# V72_CIS.net
KiCad netlist of a schematic drawn in Altium Designer
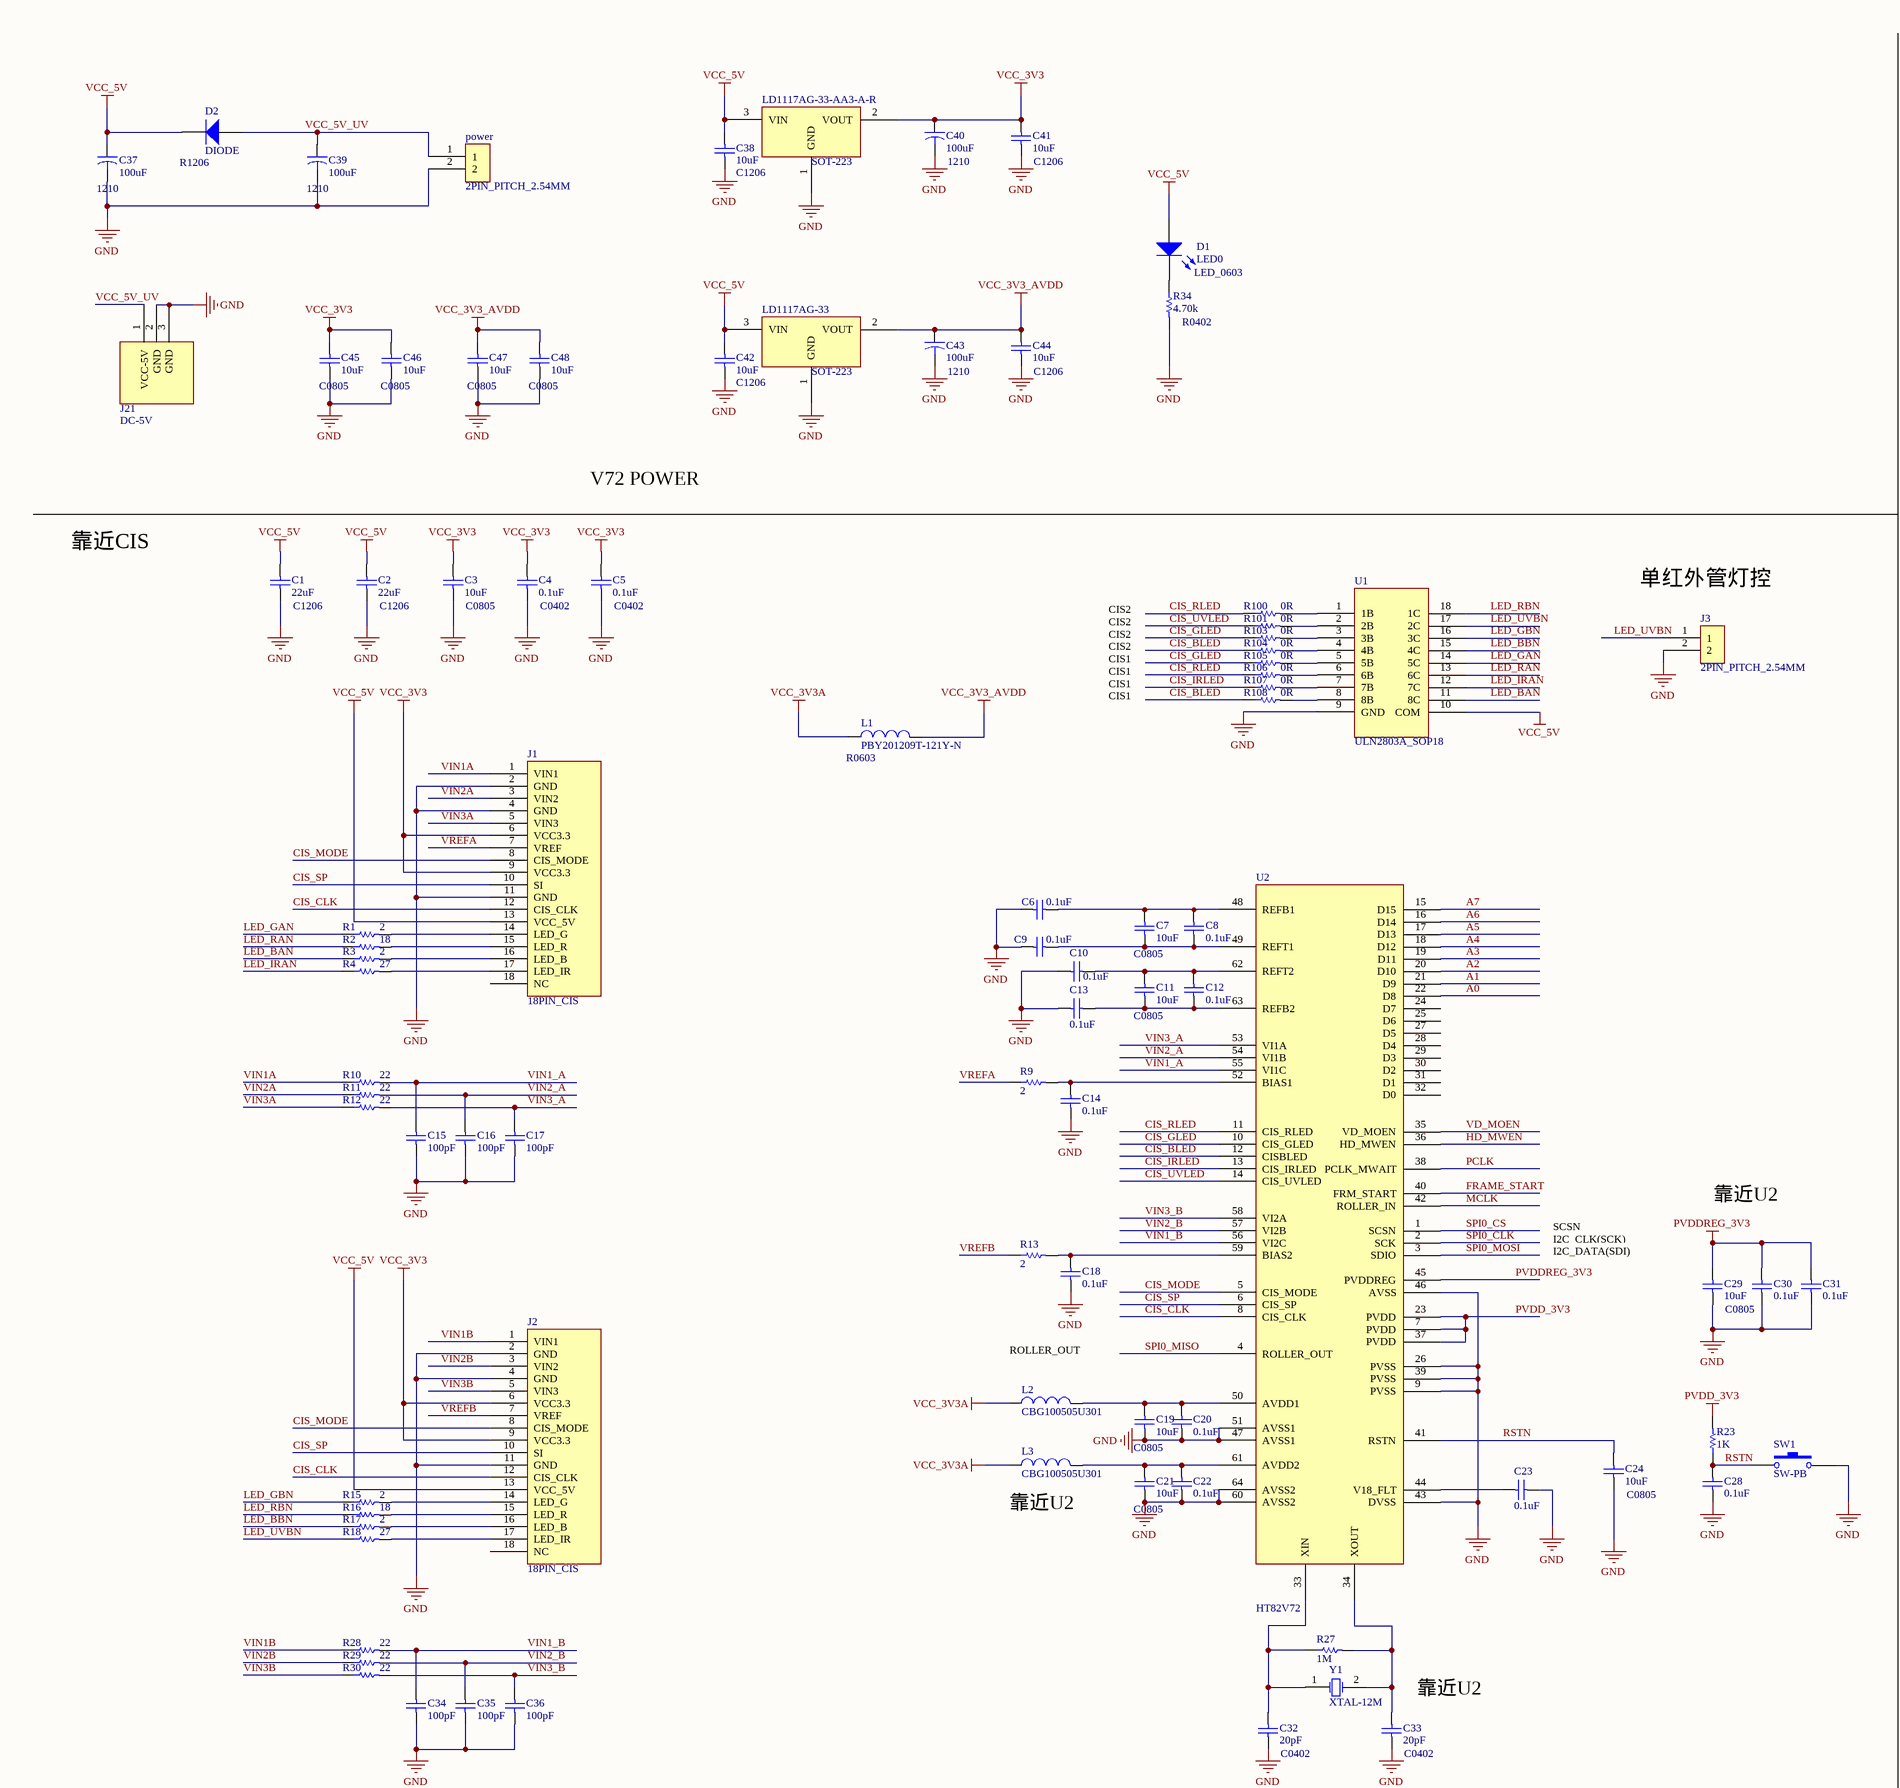
[diagram p0: V72单CIS.SchDoc, top left]
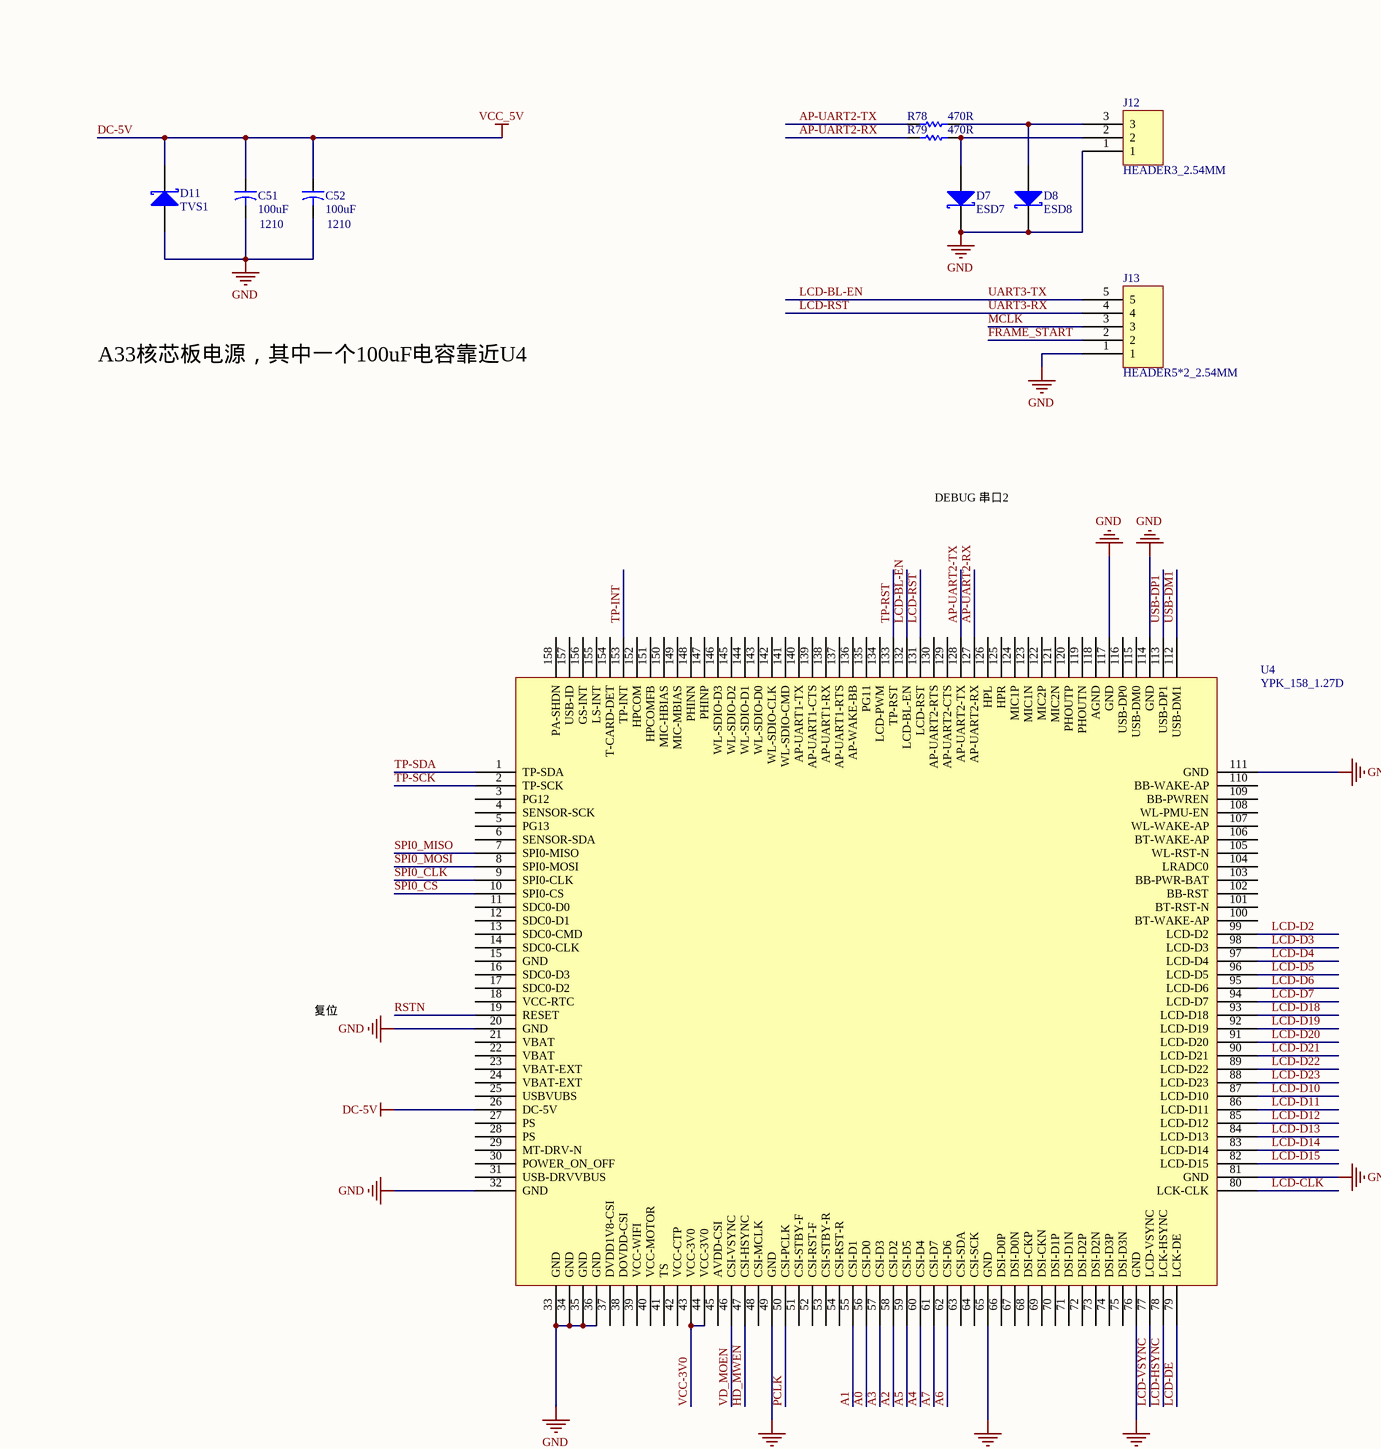
[diagram p1: V72单CIS.SchDoc, top middle]
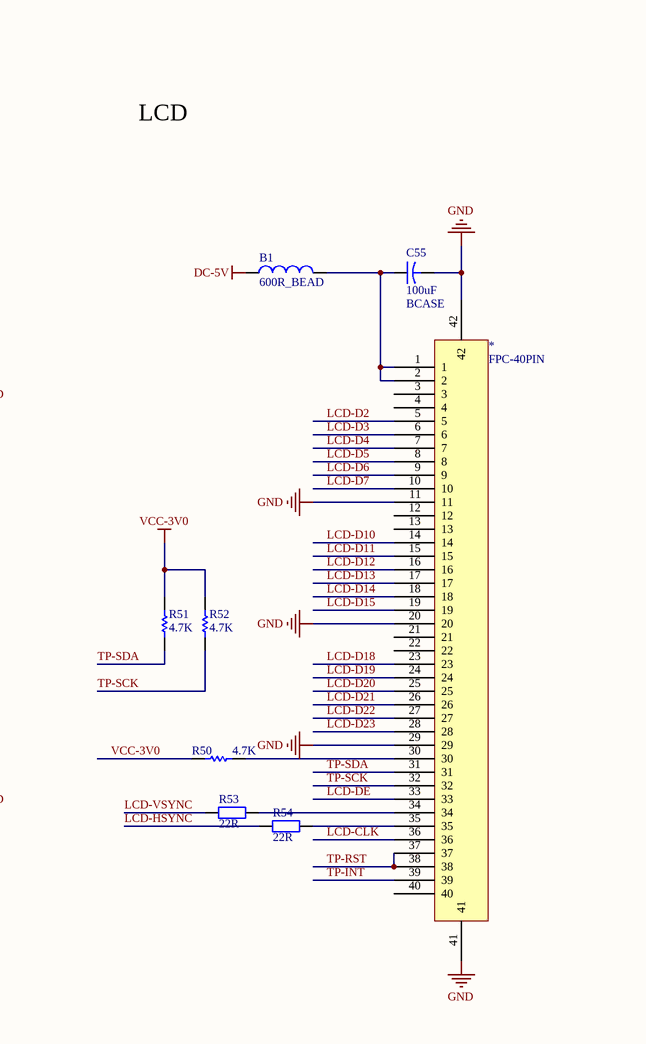
[diagram p2: V72单CIS.SchDoc, top right]
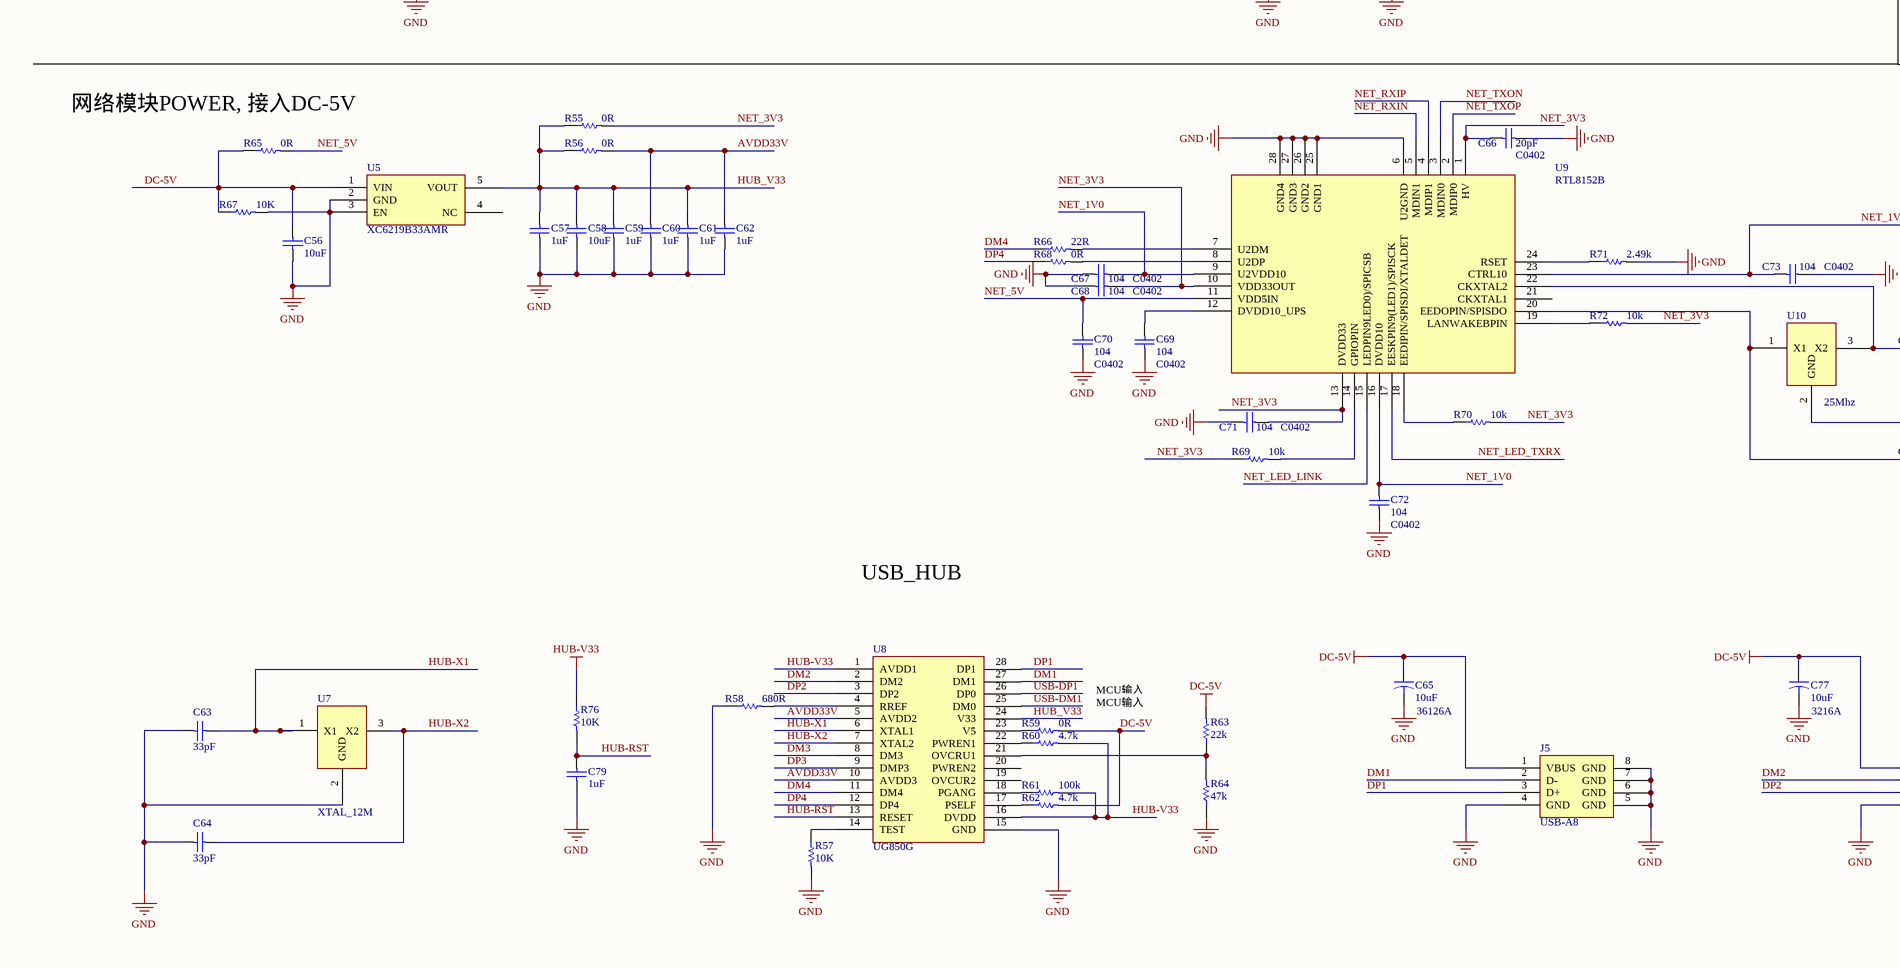
[diagram p3: V72单CIS.SchDoc, bottom left]
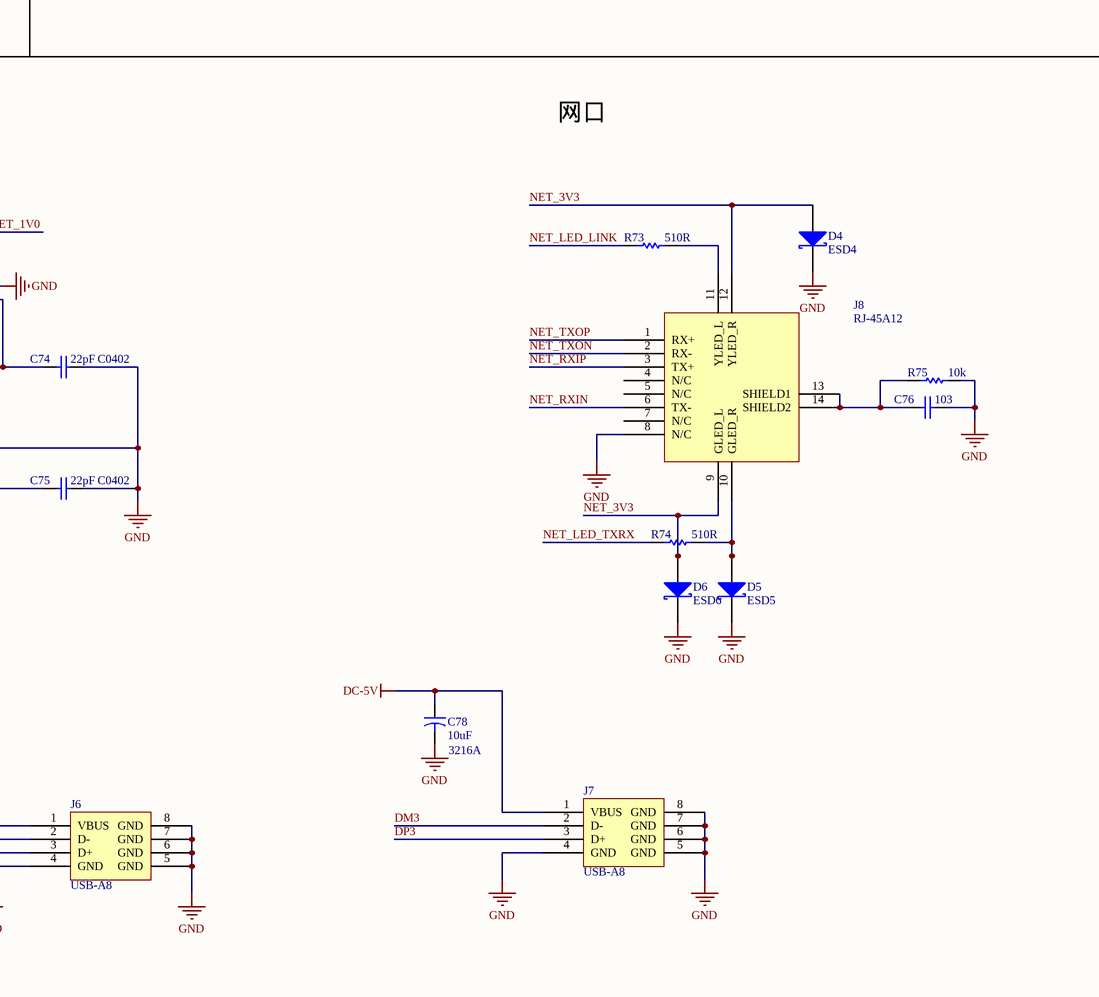
[diagram p4: V72单CIS.SchDoc, bottom middle]

(export (version "E")
  (design (tool "Eeschema 10.0.6"))
  (components
    (comp (ref "*")
      (value "FPC-40PIN")
      (footprint "FPC-40PIN")
      (libsource (lib "Integrated_Library") (part "FPC-40PIN"))
    )
    (comp (ref "B1")
      (value "600R_BEAD")
      (footprint "R0603")
      (description "Inductor")
      (fields (field (name "PUBLISHER") "Altium Limited"))
      (libsource (lib "Miscellaneous Devices") (part "Inductor"))
    )
    (comp (ref "C1")
      (value "22uF")
      (footprint "C1206")
      (description "Capacitor")
      (fields (field (name "PUBLISHER") "Altium Limited"))
      (libsource (lib "Miscellaneous Devices") (part "Cap"))
    )
    (comp (ref "C2")
      (value "22uF")
      (footprint "C1206")
      (description "Capacitor")
      (fields (field (name "PUBLISHER") "Altium Limited"))
      (libsource (lib "Miscellaneous Devices") (part "Cap"))
    )
    (comp (ref "C3")
      (value "10uF")
      (footprint "C0805")
      (description "Capacitor")
      (fields (field (name "PUBLISHER") "Altium Limited"))
      (libsource (lib "Miscellaneous Devices") (part "Cap"))
    )
    (comp (ref "C4")
      (value "0.1uF")
      (footprint "C0402")
      (description "Capacitor")
      (fields (field (name "PUBLISHER") "Altium Limited"))
      (libsource (lib "Miscellaneous Devices") (part "Cap"))
    )
    (comp (ref "C5")
      (value "0.1uF")
      (footprint "C0402")
      (description "Capacitor")
      (fields (field (name "PUBLISHER") "Altium Limited"))
      (libsource (lib "Miscellaneous Devices") (part "Cap"))
    )
    (comp (ref "C6")
      (value "0.1uF")
      (footprint "C0402")
      (description "Capacitor")
      (fields (field (name "PUBLISHER") "Altium Limited"))
      (libsource (lib "Miscellaneous Devices") (part "Cap"))
    )
    (comp (ref "C7")
      (value "10uF")
      (footprint "C0805")
      (description "Capacitor")
      (fields (field (name "PUBLISHER") "Altium Limited"))
      (libsource (lib "Miscellaneous Devices") (part "Cap"))
    )
    (comp (ref "C8")
      (value "0.1uF")
      (footprint "C0402")
      (description "Capacitor")
      (fields (field (name "PUBLISHER") "Altium Limited"))
      (libsource (lib "Miscellaneous Devices") (part "Cap"))
    )
    (comp (ref "C9")
      (value "0.1uF")
      (footprint "C0402")
      (description "Capacitor")
      (fields (field (name "PUBLISHER") "Altium Limited"))
      (libsource (lib "Miscellaneous Devices") (part "Cap"))
    )
    (comp (ref "C10")
      (value "0.1uF")
      (footprint "C0402")
      (description "Capacitor")
      (fields (field (name "PUBLISHER") "Altium Limited"))
      (libsource (lib "Miscellaneous Devices") (part "Cap"))
    )
    (comp (ref "C11")
      (value "10uF")
      (footprint "C0805")
      (description "Capacitor")
      (fields (field (name "PUBLISHER") "Altium Limited"))
      (libsource (lib "Miscellaneous Devices") (part "Cap"))
    )
    (comp (ref "C12")
      (value "0.1uF")
      (footprint "C0402")
      (description "Capacitor")
      (fields (field (name "PUBLISHER") "Altium Limited"))
      (libsource (lib "Miscellaneous Devices") (part "Cap"))
    )
    (comp (ref "C13")
      (value "0.1uF")
      (footprint "C0402")
      (description "Capacitor")
      (fields (field (name "PUBLISHER") "Altium Limited"))
      (libsource (lib "Miscellaneous Devices") (part "Cap"))
    )
    (comp (ref "C14")
      (value "0.1uF")
      (footprint "C0402")
      (description "Capacitor")
      (fields (field (name "PUBLISHER") "Altium Limited"))
      (libsource (lib "Miscellaneous Devices") (part "Cap"))
    )
    (comp (ref "C15")
      (value "100pF")
      (footprint "C0402")
      (description "Capacitor")
      (fields (field (name "PUBLISHER") "Altium Limited"))
      (libsource (lib "Miscellaneous Devices") (part "Cap"))
    )
    (comp (ref "C16")
      (value "100pF")
      (footprint "C0402")
      (description "Capacitor")
      (fields (field (name "PUBLISHER") "Altium Limited"))
      (libsource (lib "Miscellaneous Devices") (part "Cap"))
    )
    (comp (ref "C17")
      (value "100pF")
      (footprint "C0402")
      (description "Capacitor")
      (fields (field (name "PUBLISHER") "Altium Limited"))
      (libsource (lib "Miscellaneous Devices") (part "Cap"))
    )
    (comp (ref "C18")
      (value "0.1uF")
      (footprint "C0402")
      (description "Capacitor")
      (fields (field (name "PUBLISHER") "Altium Limited"))
      (libsource (lib "Miscellaneous Devices") (part "Cap"))
    )
    (comp (ref "C19")
      (value "10uF")
      (footprint "C0805")
      (description "Capacitor")
      (fields (field (name "PUBLISHER") "Altium Limited"))
      (libsource (lib "Miscellaneous Devices") (part "Cap"))
    )
    (comp (ref "C20")
      (value "0.1uF")
      (footprint "C0402")
      (description "Capacitor")
      (fields (field (name "PUBLISHER") "Altium Limited"))
      (libsource (lib "Miscellaneous Devices") (part "Cap"))
    )
    (comp (ref "C21")
      (value "10uF")
      (footprint "C0805")
      (description "Capacitor")
      (fields (field (name "PUBLISHER") "Altium Limited"))
      (libsource (lib "Miscellaneous Devices") (part "Cap"))
    )
    (comp (ref "C22")
      (value "0.1uF")
      (footprint "C0402")
      (description "Capacitor")
      (fields (field (name "PUBLISHER") "Altium Limited"))
      (libsource (lib "Miscellaneous Devices") (part "Cap"))
    )
    (comp (ref "C23")
      (value "0.1uF")
      (footprint "C0402")
      (description "Capacitor")
      (fields (field (name "PUBLISHER") "Altium Limited"))
      (libsource (lib "Miscellaneous Devices") (part "Cap"))
    )
    (comp (ref "C24")
      (value "10uF")
      (footprint "C0805")
      (description "Capacitor")
      (fields (field (name "PUBLISHER") "Altium Limited"))
      (libsource (lib "Miscellaneous Devices") (part "Cap"))
    )
    (comp (ref "C28")
      (value "0.1uF")
      (footprint "C0402")
      (description "Capacitor")
      (fields (field (name "PUBLISHER") "Altium Limited"))
      (libsource (lib "Miscellaneous Devices") (part "Cap"))
    )
    (comp (ref "C29")
      (value "10uF")
      (footprint "C0805")
      (description "Capacitor")
      (fields (field (name "PUBLISHER") "Altium Limited"))
      (libsource (lib "Miscellaneous Devices") (part "Cap"))
    )
    (comp (ref "C30")
      (value "0.1uF")
      (footprint "C0402")
      (description "Capacitor")
      (fields (field (name "PUBLISHER") "Altium Limited"))
      (libsource (lib "Miscellaneous Devices") (part "Cap"))
    )
    (comp (ref "C31")
      (value "0.1uF")
      (footprint "C0402")
      (description "Capacitor")
      (fields (field (name "PUBLISHER") "Altium Limited"))
      (libsource (lib "Miscellaneous Devices") (part "Cap"))
    )
    (comp (ref "C32")
      (value "20pF")
      (footprint "C0402")
      (description "Capacitor")
      (fields (field (name "PUBLISHER") "Altium Limited"))
      (libsource (lib "Miscellaneous Devices") (part "Cap"))
    )
    (comp (ref "C33")
      (value "20pF")
      (footprint "C0402")
      (description "Capacitor")
      (fields (field (name "PUBLISHER") "Altium Limited"))
      (libsource (lib "Miscellaneous Devices") (part "Cap"))
    )
    (comp (ref "C34")
      (value "100pF")
      (footprint "C0402")
      (description "Capacitor")
      (fields (field (name "PUBLISHER") "Altium Limited"))
      (libsource (lib "Miscellaneous Devices") (part "Cap"))
    )
    (comp (ref "C35")
      (value "100pF")
      (footprint "C0402")
      (description "Capacitor")
      (fields (field (name "PUBLISHER") "Altium Limited"))
      (libsource (lib "Miscellaneous Devices") (part "Cap"))
    )
    (comp (ref "C36")
      (value "100pF")
      (footprint "C0402")
      (description "Capacitor")
      (fields (field (name "PUBLISHER") "Altium Limited"))
      (libsource (lib "Miscellaneous Devices") (part "Cap"))
    )
    (comp (ref "C37")
      (value "100uF")
      (footprint "1210")
      (description "电容")
      (fields (field (name "PUBLISHER") "Altium Limited"))
      (libsource (lib "Miscellaneous Devices") (part "Cap2"))
    )
    (comp (ref "C38")
      (value "10uF")
      (footprint "C1206")
      (description "Capacitor")
      (fields (field (name "PUBLISHER") "Altium Limited"))
      (libsource (lib "Miscellaneous Devices") (part "Cap"))
    )
    (comp (ref "C39")
      (value "100uF")
      (footprint "1210")
      (description "Capacitor")
      (fields (field (name "PUBLISHER") "Altium Limited"))
      (libsource (lib "Miscellaneous Devices") (part "Cap2"))
    )
    (comp (ref "C40")
      (value "100uF")
      (footprint "1210")
      (description "Capacitor")
      (fields (field (name "PUBLISHER") "Altium Limited"))
      (libsource (lib "Miscellaneous Devices") (part "Cap2"))
    )
    (comp (ref "C41")
      (value "10uF")
      (footprint "C1206")
      (description "Capacitor")
      (fields (field (name "PUBLISHER") "Altium Limited"))
      (libsource (lib "Miscellaneous Devices") (part "Cap"))
    )
    (comp (ref "C42")
      (value "10uF")
      (footprint "C1206")
      (description "Capacitor")
      (fields (field (name "PUBLISHER") "Altium Limited"))
      (libsource (lib "Miscellaneous Devices") (part "Cap"))
    )
    (comp (ref "C43")
      (value "100uF")
      (footprint "1210")
      (description "Capacitor")
      (fields (field (name "PUBLISHER") "Altium Limited"))
      (libsource (lib "Miscellaneous Devices") (part "Cap2"))
    )
    (comp (ref "C44")
      (value "10uF")
      (footprint "C1206")
      (description "Capacitor")
      (fields (field (name "PUBLISHER") "Altium Limited"))
      (libsource (lib "Miscellaneous Devices") (part "Cap"))
    )
    (comp (ref "C45")
      (value "10uF")
      (footprint "C0805")
      (description "Capacitor")
      (fields (field (name "PUBLISHER") "Altium Limited"))
      (libsource (lib "Miscellaneous Devices") (part "Cap"))
    )
    (comp (ref "C46")
      (value "10uF")
      (footprint "C0805")
      (description "Capacitor")
      (fields (field (name "PUBLISHER") "Altium Limited"))
      (libsource (lib "Miscellaneous Devices") (part "Cap"))
    )
    (comp (ref "C47")
      (value "10uF")
      (footprint "C0805")
      (description "Capacitor")
      (fields (field (name "PUBLISHER") "Altium Limited"))
      (libsource (lib "Miscellaneous Devices") (part "Cap"))
    )
    (comp (ref "C48")
      (value "10uF")
      (footprint "C0805")
      (description "Capacitor")
      (fields (field (name "PUBLISHER") "Altium Limited"))
      (libsource (lib "Miscellaneous Devices") (part "Cap"))
    )
    (comp (ref "C51")
      (value "100uF")
      (footprint "1210")
      (description "Capacitor")
      (fields (field (name "PUBLISHER") "Altium Limited"))
      (libsource (lib "Miscellaneous Devices") (part "Cap2"))
    )
    (comp (ref "C52")
      (value "100uF")
      (footprint "1210")
      (description "Capacitor")
      (fields (field (name "PUBLISHER") "Altium Limited"))
      (libsource (lib "Miscellaneous Devices") (part "Cap2"))
    )
    (comp (ref "C55")
      (value "100uF")
      (footprint "BCASE")
      (description "Capacitor")
      (fields (field (name "PUBLISHER") "Altium Limited"))
      (libsource (lib "Miscellaneous Devices") (part "Cap2"))
    )
    (comp (ref "C56")
      (value "10uF")
      (footprint "0603A")
      (description "Capacitor")
      (fields (field (name "PUBLISHER") "Altium Limited"))
      (libsource (lib "Miscellaneous Devices") (part "Cap"))
    )
    (comp (ref "C57")
      (value "1uF")
      (footprint "0603A")
      (description "Capacitor")
      (fields (field (name "PUBLISHER") "Altium Limited"))
      (libsource (lib "Miscellaneous Devices") (part "Cap"))
    )
    (comp (ref "C58")
      (value "10uF")
      (footprint "0603A")
      (description "Capacitor")
      (fields (field (name "PUBLISHER") "Altium Limited"))
      (libsource (lib "Miscellaneous Devices") (part "Cap"))
    )
    (comp (ref "C59")
      (value "1uF")
      (footprint "0603A")
      (description "Capacitor")
      (fields (field (name "PUBLISHER") "Altium Limited"))
      (libsource (lib "Miscellaneous Devices") (part "Cap"))
    )
    (comp (ref "C60")
      (value "1uF")
      (footprint "0603A")
      (description "Capacitor")
      (fields (field (name "PUBLISHER") "Altium Limited"))
      (libsource (lib "Miscellaneous Devices") (part "Cap"))
    )
    (comp (ref "C61")
      (value "1uF")
      (footprint "0603A")
      (description "Capacitor")
      (fields (field (name "PUBLISHER") "Altium Limited"))
      (libsource (lib "Miscellaneous Devices") (part "Cap"))
    )
    (comp (ref "C62")
      (value "1uF")
      (footprint "0603A")
      (description "Capacitor")
      (fields (field (name "PUBLISHER") "Altium Limited"))
      (libsource (lib "Miscellaneous Devices") (part "Cap"))
    )
    (comp (ref "C63")
      (value "33pF")
      (footprint "0603A")
      (description "Capacitor")
      (fields (field (name "PUBLISHER") "Altium Limited"))
      (libsource (lib "Miscellaneous Devices") (part "Cap"))
    )
    (comp (ref "C64")
      (value "33pF")
      (footprint "0603A")
      (description "Capacitor")
      (fields (field (name "PUBLISHER") "Altium Limited"))
      (libsource (lib "Miscellaneous Devices") (part "Cap"))
    )
    (comp (ref "C65")
      (value "10uF")
      (footprint "36126A")
      (description "Capacitor")
      (fields (field (name "PUBLISHER") "Altium Limited"))
      (libsource (lib "Miscellaneous Devices") (part "Cap2"))
    )
    (comp (ref "C66")
      (value "20pF")
      (footprint "C0402")
      (description "Capacitor")
      (fields (field (name "PUBLISHER") "Altium Limited"))
      (libsource (lib "Miscellaneous Devices") (part "Cap"))
    )
    (comp (ref "C67")
      (value "104")
      (footprint "C0402")
      (description "Capacitor")
      (fields (field (name "PUBLISHER") "Altium Limited"))
      (libsource (lib "Miscellaneous Devices") (part "Cap"))
    )
    (comp (ref "C68")
      (value "104")
      (footprint "C0402")
      (description "Capacitor")
      (fields (field (name "PUBLISHER") "Altium Limited"))
      (libsource (lib "Miscellaneous Devices") (part "Cap"))
    )
    (comp (ref "C69")
      (value "104")
      (footprint "C0402")
      (description "Capacitor")
      (fields (field (name "PUBLISHER") "Altium Limited"))
      (libsource (lib "Miscellaneous Devices") (part "Cap"))
    )
    (comp (ref "C70")
      (value "104")
      (footprint "C0402")
      (description "Capacitor")
      (fields (field (name "PUBLISHER") "Altium Limited"))
      (libsource (lib "Miscellaneous Devices") (part "Cap"))
    )
    (comp (ref "C71")
      (value "104")
      (footprint "C0402")
      (description "Capacitor")
      (fields (field (name "PUBLISHER") "Altium Limited"))
      (libsource (lib "Miscellaneous Devices") (part "Cap"))
    )
    (comp (ref "C72")
      (value "104")
      (footprint "C0402")
      (description "Capacitor")
      (fields (field (name "PUBLISHER") "Altium Limited"))
      (libsource (lib "Miscellaneous Devices") (part "Cap"))
    )
    (comp (ref "C73")
      (value "104")
      (footprint "C0402")
      (description "Capacitor")
      (fields (field (name "PUBLISHER") "Altium Limited"))
      (libsource (lib "Miscellaneous Devices") (part "Cap"))
    )
    (comp (ref "C74")
      (value "22pF")
      (footprint "C0402")
      (description "Capacitor")
      (fields (field (name "PUBLISHER") "Altium Limited"))
      (libsource (lib "Miscellaneous Devices") (part "Cap"))
    )
    (comp (ref "C75")
      (value "22pF")
      (footprint "C0402")
      (description "Capacitor")
      (fields (field (name "PUBLISHER") "Altium Limited"))
      (libsource (lib "Miscellaneous Devices") (part "Cap"))
    )
    (comp (ref "C76")
      (value "103")
      (footprint "C0402")
      (description "Capacitor")
      (fields (field (name "PUBLISHER") "Altium Limited"))
      (libsource (lib "Miscellaneous Devices") (part "Cap"))
    )
    (comp (ref "C77")
      (value "10uF")
      (footprint "3216A")
      (description "Capacitor")
      (fields (field (name "PUBLISHER") "Altium Limited"))
      (libsource (lib "Miscellaneous Devices") (part "Cap2"))
    )
    (comp (ref "C78")
      (value "10uF")
      (footprint "3216A")
      (description "Capacitor")
      (fields (field (name "PUBLISHER") "Altium Limited"))
      (libsource (lib "Miscellaneous Devices") (part "Cap2"))
    )
    (comp (ref "C79")
      (value "1uF")
      (footprint "0603A")
      (description "Capacitor")
      (fields (field (name "PUBLISHER") "Altium Limited"))
      (libsource (lib "Miscellaneous Devices") (part "Cap"))
    )
    (comp (ref "D1")
      (value "LED0")
      (footprint "LED_0603")
      (description "Typical INFRARED GaAs LED")
      (fields (field (name "FOOTPRIINT") "LED_0603") (field (name "PUBLISHER") "Altium Limited"))
      (libsource (lib "Miscellaneous Devices") (part "LED0"))
    )
    (comp (ref "D2")
      (value "DIODE")
      (footprint "R1206")
      (description "Computer Diode")
      (fields (field (name "PUBLISHER") "Altium Limited"))
      (libsource (lib "Miscellaneous Devices") (part "Diode 1N4149"))
    )
    (comp (ref "D4")
      (value "ESD4")
      (footprint "LED_0603")
      (description "Silicon AF Schottky Diode for High-Speed Switching")
      (fields (field (name "PUBLISHER") "Altium Limited"))
      (libsource (lib "Miscellaneous Devices") (part "Diode BAS70"))
    )
    (comp (ref "D5")
      (value "ESD5")
      (footprint "LED_0603")
      (description "Silicon AF Schottky Diode for High-Speed Switching")
      (fields (field (name "PUBLISHER") "Altium Limited"))
      (libsource (lib "Miscellaneous Devices") (part "Diode BAS70"))
    )
    (comp (ref "D6")
      (value "ESD6")
      (footprint "LED_0603")
      (description "Silicon AF Schottky Diode for High-Speed Switching")
      (fields (field (name "PUBLISHER") "Altium Limited"))
      (libsource (lib "Miscellaneous Devices") (part "Diode BAS70"))
    )
    (comp (ref "D7")
      (value "ESD7")
      (footprint "LED_0603")
      (description "Silicon AF Schottky Diode for High-Speed Switching")
      (fields (field (name "PUBLISHER") "Altium Limited"))
      (libsource (lib "Miscellaneous Devices") (part "Diode BAS70"))
    )
    (comp (ref "D8")
      (value "ESD8")
      (footprint "LED_0603")
      (description "Silicon AF Schottky Diode for High-Speed Switching")
      (fields (field (name "PUBLISHER") "Altium Limited"))
      (libsource (lib "Miscellaneous Devices") (part "Diode BAS70"))
    )
    (comp (ref "D11")
      (value "TVS1")
      (footprint "SMB")
      (description "TVS二极管5V")
      (fields (field (name "PUBLISHER") "Altium Limited"))
      (libsource (lib "Miscellaneous Devices") (part "D Schottky"))
    )
    (comp (ref "J1")
      (value "18PIN_CIS")
      (footprint "18PIN_FPC")
      (libsource (lib "Integrated_Library") (part "18PIN_CIS"))
    )
    (comp (ref "J2")
      (value "18PIN_CIS")
      (footprint "18PIN_FPC")
      (libsource (lib "Integrated_Library") (part "18PIN_CIS"))
    )
    (comp (ref "J3")
      (value "2PIN_PITCH_2.54MM")
      (footprint "2PIN_PITCH_2.54MM")
      (libsource (lib "Integrated_Library") (part "2PIN_PITCH_2.54MM"))
    )
    (comp (ref "J5")
      (value "USB-A8")
      (footprint "USB-A8")
      (libsource (lib "Integrated_Library") (part "USB-A8"))
    )
    (comp (ref "J6")
      (value "USB-A8")
      (footprint "USB-A8")
      (libsource (lib "Integrated_Library") (part "USB-A8"))
    )
    (comp (ref "J7")
      (value "USB-A8")
      (footprint "USB-A8")
      (libsource (lib "Integrated_Library") (part "USB-A8"))
    )
    (comp (ref "J8")
      (value "RJ-45A12")
      (footprint "RJ-45A12")
      (libsource (lib "Integrated_Library") (part "RJ-45A12"))
    )
    (comp (ref "J12")
      (value "HEADER3_2.54MM")
      (footprint "HEADER3_2.54MM")
      (libsource (lib "Integrated_Library") (part "HEADER3_2.54MM"))
    )
    (comp (ref "J13")
      (value "HEADER5*2_2.54MM")
      (footprint "HEADER5_2.54MM")
      (libsource (lib "Integrated_Library") (part "HEADER5*2_2.54MM"))
    )
    (comp (ref "J21")
      (value "DC-5V")
      (footprint "DC-5V")
      (libsource (lib "Integrated_Library") (part "DC-5V"))
    )
    (comp (ref "L1")
      (value "PBY201209T-121Y-N")
      (footprint "R0603")
      (description "电感")
      (fields (field (name "PUBLISHER") "Altium Limited"))
      (libsource (lib "Miscellaneous Devices") (part "Inductor"))
    )
    (comp (ref "L2")
      (value "CBG100505U301")
      (footprint "R0603")
      (description "Inductor")
      (fields (field (name "PUBLISHER") "Altium Limited"))
      (libsource (lib "Miscellaneous Devices") (part "Inductor"))
    )
    (comp (ref "L3")
      (value "CBG100505U301")
      (footprint "R0603")
      (description "Inductor")
      (fields (field (name "PUBLISHER") "Altium Limited"))
      (libsource (lib "Miscellaneous Devices") (part "Inductor"))
    )
    (comp (ref "LD1117AG-33")
      (value "SOT-223")
      (footprint "SOT-223")
      (libsource (lib "Integrated_Library") (part "LD1117S33TR"))
    )
    (comp (ref "LD1117AG-33-AA3-A-R")
      (value "SOT-223")
      (footprint "SOT-223")
      (libsource (lib "Integrated_Library") (part "LD1117S33TR"))
    )
    (comp (ref "power")
      (value "2PIN_PITCH_2.54MM")
      (footprint "2PIN_PITCH_2.54MM")
      (libsource (lib "Integrated_Library") (part "2PIN_PITCH_2.54MM"))
    )
    (comp (ref "R1")
      (value "2")
      (footprint "R0603")
      (description "Resistor")
      (fields (field (name "PUBLISHER") "Altium Limited"))
      (libsource (lib "Miscellaneous Devices") (part "Res1"))
    )
    (comp (ref "R2")
      (value "18")
      (footprint "R0603")
      (description "Resistor")
      (fields (field (name "PUBLISHER") "Altium Limited"))
      (libsource (lib "Miscellaneous Devices") (part "Res1"))
    )
    (comp (ref "R3")
      (value "2")
      (footprint "R0603")
      (description "Resistor")
      (fields (field (name "PUBLISHER") "Altium Limited"))
      (libsource (lib "Miscellaneous Devices") (part "Res1"))
    )
    (comp (ref "R4")
      (value "27")
      (footprint "R0603")
      (description "Resistor")
      (fields (field (name "PUBLISHER") "Altium Limited"))
      (libsource (lib "Miscellaneous Devices") (part "Res1"))
    )
    (comp (ref "R9")
      (value "2")
      (footprint "R0603")
      (description "Resistor")
      (fields (field (name "PUBLISHER") "Altium Limited"))
      (libsource (lib "Miscellaneous Devices") (part "Res1"))
    )
    (comp (ref "R10")
      (value "22")
      (footprint "R0603")
      (description "Resistor")
      (fields (field (name "PUBLISHER") "Altium Limited"))
      (libsource (lib "Miscellaneous Devices") (part "Res1"))
    )
    (comp (ref "R11")
      (value "22")
      (footprint "R0603")
      (description "Resistor")
      (fields (field (name "PUBLISHER") "Altium Limited"))
      (libsource (lib "Miscellaneous Devices") (part "Res1"))
    )
    (comp (ref "R12")
      (value "22")
      (footprint "R0603")
      (description "Resistor")
      (fields (field (name "PUBLISHER") "Altium Limited"))
      (libsource (lib "Miscellaneous Devices") (part "Res1"))
    )
    (comp (ref "R13")
      (value "2")
      (footprint "R0603")
      (description "Resistor")
      (fields (field (name "PUBLISHER") "Altium Limited"))
      (libsource (lib "Miscellaneous Devices") (part "Res1"))
    )
    (comp (ref "R15")
      (value "2")
      (footprint "R0603")
      (description "Resistor")
      (fields (field (name "PUBLISHER") "Altium Limited"))
      (libsource (lib "Miscellaneous Devices") (part "Res1"))
    )
    (comp (ref "R16")
      (value "18")
      (footprint "R0603")
      (description "Resistor")
      (fields (field (name "PUBLISHER") "Altium Limited"))
      (libsource (lib "Miscellaneous Devices") (part "Res1"))
    )
    (comp (ref "R17")
      (value "2")
      (footprint "R0603")
      (description "Resistor")
      (fields (field (name "PUBLISHER") "Altium Limited"))
      (libsource (lib "Miscellaneous Devices") (part "Res1"))
    )
    (comp (ref "R18")
      (value "27")
      (footprint "R0603")
      (description "Resistor")
      (fields (field (name "PUBLISHER") "Altium Limited"))
      (libsource (lib "Miscellaneous Devices") (part "Res1"))
    )
    (comp (ref "R23")
      (value "1K")
      (footprint "R0603")
      (description "Resistor")
      (fields (field (name "PUBLISHER") "Altium Limited"))
      (libsource (lib "Miscellaneous Devices") (part "Res1"))
    )
    (comp (ref "R27")
      (value "1M")
      (footprint "R0603")
      (description "Resistor")
      (fields (field (name "PUBLISHER") "Altium Limited"))
      (libsource (lib "Miscellaneous Devices") (part "Res1"))
    )
    (comp (ref "R28")
      (value "22")
      (footprint "R0603")
      (description "Resistor")
      (fields (field (name "PUBLISHER") "Altium Limited"))
      (libsource (lib "Miscellaneous Devices") (part "Res1"))
    )
    (comp (ref "R29")
      (value "22")
      (footprint "R0603")
      (description "Resistor")
      (fields (field (name "PUBLISHER") "Altium Limited"))
      (libsource (lib "Miscellaneous Devices") (part "Res1"))
    )
    (comp (ref "R30")
      (value "22")
      (footprint "R0603")
      (description "Resistor")
      (fields (field (name "PUBLISHER") "Altium Limited"))
      (libsource (lib "Miscellaneous Devices") (part "Res1"))
    )
    (comp (ref "R34")
      (value "4.70k")
      (footprint "R0402")
      (description "Resistor")
      (fields (field (name "PUBLISHER") "Altium Limited"))
      (libsource (lib "Miscellaneous Devices") (part "Res1"))
    )
    (comp (ref "R50")
      (value "4.7K")
      (footprint "R0603")
      (description "Resistor")
      (fields (field (name "PUBLISHER") "Altium Limited"))
      (libsource (lib "Miscellaneous Devices") (part "Res1"))
    )
    (comp (ref "R51")
      (value "4.7K")
      (footprint "R0603")
      (description "Resistor")
      (fields (field (name "PUBLISHER") "Altium Limited"))
      (libsource (lib "Miscellaneous Devices") (part "Res1"))
    )
    (comp (ref "R52")
      (value "4.7K")
      (footprint "R0603")
      (description "Resistor")
      (fields (field (name "PUBLISHER") "Altium Limited"))
      (libsource (lib "Miscellaneous Devices") (part "Res1"))
    )
    (comp (ref "R53")
      (value "22R")
      (footprint "R0603")
      (description "Resistor")
      (fields (field (name "PUBLISHER") "Altium Limited"))
      (libsource (lib "Miscellaneous Devices") (part "Res2"))
    )
    (comp (ref "R54")
      (value "22R")
      (footprint "R0603")
      (description "Resistor")
      (fields (field (name "PUBLISHER") "Altium Limited"))
      (libsource (lib "Miscellaneous Devices") (part "Res2"))
    )
    (comp (ref "R55")
      (value "0R")
      (footprint "R0603")
      (description "Resistor")
      (fields (field (name "PUBLISHER") "Altium Limited"))
      (libsource (lib "Miscellaneous Devices") (part "Res1"))
    )
    (comp (ref "R56")
      (value "0R")
      (footprint "R0603")
      (description "Resistor")
      (fields (field (name "PUBLISHER") "Altium Limited"))
      (libsource (lib "Miscellaneous Devices") (part "Res1"))
    )
    (comp (ref "R57")
      (value "10K")
      (footprint "R0603")
      (description "Resistor")
      (fields (field (name "PUBLISHER") "Altium Limited"))
      (libsource (lib "Miscellaneous Devices") (part "Res1"))
    )
    (comp (ref "R58")
      (value "680R")
      (footprint "R0603")
      (description "Resistor")
      (fields (field (name "PUBLISHER") "Altium Limited"))
      (libsource (lib "Miscellaneous Devices") (part "Res1"))
    )
    (comp (ref "R59")
      (value "0R")
      (footprint "R0603")
      (description "Resistor")
      (fields (field (name "PUBLISHER") "Altium Limited"))
      (libsource (lib "Miscellaneous Devices") (part "Res1"))
    )
    (comp (ref "R60")
      (value "4.7k")
      (footprint "R0603")
      (description "Resistor")
      (fields (field (name "PUBLISHER") "Altium Limited"))
      (libsource (lib "Miscellaneous Devices") (part "Res1"))
    )
    (comp (ref "R61")
      (value "100k")
      (footprint "R0603")
      (description "Resistor")
      (fields (field (name "PUBLISHER") "Altium Limited"))
      (libsource (lib "Miscellaneous Devices") (part "Res1"))
    )
    (comp (ref "R62")
      (value "4.7k")
      (footprint "R0603")
      (description "Resistor")
      (fields (field (name "PUBLISHER") "Altium Limited"))
      (libsource (lib "Miscellaneous Devices") (part "Res1"))
    )
    (comp (ref "R63")
      (value "22k")
      (footprint "0603A")
      (description "Resistor")
      (fields (field (name "PUBLISHER") "Altium Limited"))
      (libsource (lib "Miscellaneous Devices") (part "Res1"))
    )
    (comp (ref "R64")
      (value "47k")
      (footprint "0603A")
      (description "Resistor")
      (fields (field (name "PUBLISHER") "Altium Limited"))
      (libsource (lib "Miscellaneous Devices") (part "Res1"))
    )
    (comp (ref "R65")
      (value "0R")
      (footprint "R0603")
      (description "Resistor")
      (fields (field (name "PUBLISHER") "Altium Limited"))
      (libsource (lib "Miscellaneous Devices") (part "Res1"))
    )
    (comp (ref "R66")
      (value "22R")
      (footprint "AXIAL-0.3")
      (description "Resistor")
      (fields (field (name "PUBLISHER") "Altium Limited"))
      (libsource (lib "Miscellaneous Devices") (part "Res1"))
    )
    (comp (ref "R67")
      (value "10K")
      (footprint "R0603")
      (description "Resistor")
      (fields (field (name "PUBLISHER") "Altium Limited"))
      (libsource (lib "Miscellaneous Devices") (part "Res1"))
    )
    (comp (ref "R68")
      (value "0R")
      (footprint "AXIAL-0.3")
      (description "Resistor")
      (fields (field (name "PUBLISHER") "Altium Limited"))
      (libsource (lib "Miscellaneous Devices") (part "Res1"))
    )
    (comp (ref "R69")
      (value "10k")
      (footprint "AXIAL-0.3")
      (description "Resistor")
      (fields (field (name "PUBLISHER") "Altium Limited"))
      (libsource (lib "Miscellaneous Devices") (part "Res1"))
    )
    (comp (ref "R70")
      (value "10k")
      (footprint "AXIAL-0.3")
      (description "Resistor")
      (fields (field (name "PUBLISHER") "Altium Limited"))
      (libsource (lib "Miscellaneous Devices") (part "Res1"))
    )
    (comp (ref "R71")
      (value "2.49k")
      (footprint "AXIAL-0.3")
      (description "Resistor")
      (fields (field (name "PUBLISHER") "Altium Limited"))
      (libsource (lib "Miscellaneous Devices") (part "Res1"))
    )
    (comp (ref "R72")
      (value "10k")
      (footprint "AXIAL-0.3")
      (description "Resistor")
      (fields (field (name "PUBLISHER") "Altium Limited"))
      (libsource (lib "Miscellaneous Devices") (part "Res1"))
    )
    (comp (ref "R73")
      (value "510R")
      (footprint "AXIAL-0.3")
      (description "Resistor")
      (fields (field (name "PUBLISHER") "Altium Limited"))
      (libsource (lib "Miscellaneous Devices") (part "Res1"))
    )
    (comp (ref "R74")
      (value "510R")
      (footprint "AXIAL-0.3")
      (description "Resistor")
      (fields (field (name "PUBLISHER") "Altium Limited"))
      (libsource (lib "Miscellaneous Devices") (part "Res1"))
    )
    (comp (ref "R75")
      (value "10k")
      (footprint "AXIAL-0.3")
      (description "Resistor")
      (fields (field (name "PUBLISHER") "Altium Limited"))
      (libsource (lib "Miscellaneous Devices") (part "Res1"))
    )
    (comp (ref "R76")
      (value "10K")
      (footprint "0603A")
      (description "Resistor")
      (fields (field (name "PUBLISHER") "Altium Limited"))
      (libsource (lib "Miscellaneous Devices") (part "Res1"))
    )
    (comp (ref "R78")
      (value "470R")
      (footprint "R0603")
      (description "Resistor")
      (fields (field (name "PUBLISHER") "Altium Limited"))
      (libsource (lib "Miscellaneous Devices") (part "Res1"))
    )
    (comp (ref "R79")
      (value "470R")
      (footprint "R0603")
      (description "Resistor")
      (fields (field (name "PUBLISHER") "Altium Limited"))
      (libsource (lib "Miscellaneous Devices") (part "Res1"))
    )
    (comp (ref "R100")
      (value "0R")
      (footprint "R0603")
      (description "Resistor")
      (fields (field (name "PUBLISHER") "Altium Limited"))
      (libsource (lib "Miscellaneous Devices") (part "Res1"))
    )
    (comp (ref "R101")
      (value "0R")
      (footprint "R0603")
      (description "Resistor")
      (fields (field (name "PUBLISHER") "Altium Limited"))
      (libsource (lib "Miscellaneous Devices") (part "Res1"))
    )
    (comp (ref "R103")
      (value "0R")
      (footprint "R0603")
      (description "Resistor")
      (fields (field (name "PUBLISHER") "Altium Limited"))
      (libsource (lib "Miscellaneous Devices") (part "Res1"))
    )
    (comp (ref "R104")
      (value "0R")
      (footprint "R0603")
      (description "Resistor")
      (fields (field (name "PUBLISHER") "Altium Limited"))
      (libsource (lib "Miscellaneous Devices") (part "Res1"))
    )
    (comp (ref "R105")
      (value "0R")
      (footprint "R0603")
      (description "Resistor")
      (fields (field (name "PUBLISHER") "Altium Limited"))
      (libsource (lib "Miscellaneous Devices") (part "Res1"))
    )
    (comp (ref "R106")
      (value "0R")
      (footprint "R0603")
      (description "Resistor")
      (fields (field (name "PUBLISHER") "Altium Limited"))
      (libsource (lib "Miscellaneous Devices") (part "Res1"))
    )
    (comp (ref "R107")
      (value "0R")
      (footprint "R0603")
      (description "Resistor")
      (fields (field (name "PUBLISHER") "Altium Limited"))
      (libsource (lib "Miscellaneous Devices") (part "Res1"))
    )
    (comp (ref "R108")
      (value "0R")
      (footprint "R0603")
      (description "Resistor")
      (fields (field (name "PUBLISHER") "Altium Limited"))
      (libsource (lib "Miscellaneous Devices") (part "Res1"))
    )
    (comp (ref "SW1")
      (value "SW-PB")
      (footprint "SWSW-2P-6.5M")
      (description "Switch")
      (fields (field (name "PUBLISHER") "Altium Limited"))
      (libsource (lib "Miscellaneous Devices") (part "SW-PB"))
    )
    (comp (ref "U1")
      (value "ULN2803A_SOP18")
      (footprint "ULN2803A")
      (libsource (lib "Integrated_Library") (part "ULN2803A_SOP18"))
    )
    (comp (ref "U2")
      (value "HT82V72")
      (footprint "HT82V72")
      (libsource (lib "Integrated_Library") (part "HT82V72"))
    )
    (comp (ref "U4")
      (value "YPK_158_1.27D")
      (footprint "YPK_158_1.27D")
      (libsource (lib "Integrated_Library") (part "YPK_158_1.27D"))
    )
    (comp (ref "U5")
      (value "XC6219B33AMR")
      (footprint "XC6219B33AMR")
      (libsource (lib "Integrated_Library") (part "XC6219B33AMR"))
    )
    (comp (ref "U7")
      (value "XTAL_12M")
      (footprint "XTAL")
      (libsource (lib "Integrated_Library") (part "XTAL_12M"))
    )
    (comp (ref "U8")
      (value "UG850G")
      (footprint "GL850G")
      (libsource (lib "Integrated_Library") (part "UG850G"))
    )
    (comp (ref "U9")
      (value "RTL8152B")
      (footprint "RTL8723BS")
      (libsource (lib "Integrated_Library") (part "RTL8152B"))
    )
    (comp (ref "U10")
      (value "25Mhz")
      (footprint "XTAL")
      (libsource (lib "Integrated_Library") (part "XTAL_12M"))
    )
    (comp (ref "Y1")
      (value "XTAL-12M")
      (footprint "XTAL8M")
      (description "Crystal Oscillator")
      (fields (field (name "PUBLISHER") "Altium Limited"))
      (libsource (lib "Miscellaneous Devices") (part "XTAL"))
    )
  )
  (nets
    (net (code "1") (name "/A0") (class "Default")
      (node (ref "U2") (pin "22") (pinfunction "D8_22") (pintype "passive"))
      (node (ref "U4") (pin "56") (pinfunction "CSI-D0_56") (pintype "passive"))
    )
    (net (code "2") (name "/A1") (class "Default")
      (node (ref "U2") (pin "21") (pinfunction "D9_21") (pintype "passive"))
      (node (ref "U4") (pin "55") (pinfunction "CSI-D1_55") (pintype "passive"))
    )
    (net (code "3") (name "/A2") (class "Default")
      (node (ref "U2") (pin "20") (pinfunction "D10_20") (pintype "passive"))
      (node (ref "U4") (pin "58") (pinfunction "CSI-D2_58") (pintype "passive"))
    )
    (net (code "4") (name "/A3") (class "Default")
      (node (ref "U2") (pin "19") (pinfunction "D11_19") (pintype "passive"))
      (node (ref "U4") (pin "57") (pinfunction "CSI-D3_57") (pintype "passive"))
    )
    (net (code "5") (name "/A4") (class "Default")
      (node (ref "U2") (pin "18") (pinfunction "D12_18") (pintype "passive"))
      (node (ref "U4") (pin "60") (pinfunction "CSI-D4_60") (pintype "passive"))
    )
    (net (code "6") (name "/A5") (class "Default")
      (node (ref "U2") (pin "17") (pinfunction "D13_17") (pintype "passive"))
      (node (ref "U4") (pin "59") (pinfunction "CSI-D5_59") (pintype "passive"))
    )
    (net (code "7") (name "/A6") (class "Default")
      (node (ref "U2") (pin "16") (pinfunction "D14_16") (pintype "passive"))
      (node (ref "U4") (pin "62") (pinfunction "CSI-D6_62") (pintype "passive"))
    )
    (net (code "8") (name "/A7") (class "Default")
      (node (ref "U2") (pin "15") (pinfunction "D15_15") (pintype "passive"))
      (node (ref "U4") (pin "61") (pinfunction "CSI-D7_61") (pintype "passive"))
    )
    (net (code "9") (name "/AP-UART2-RX") (class "Default")
      (node (ref "R79") (pin "1") (pinfunction "1_1") (pintype "passive"))
      (node (ref "U4") (pin "127") (pinfunction "AP-UART2-RX_127") (pintype "passive"))
    )
    (net (code "10") (name "/AP-UART2-TX") (class "Default")
      (node (ref "R78") (pin "1") (pinfunction "1_1") (pintype "passive"))
      (node (ref "U4") (pin "128") (pinfunction "AP-UART2-TX_128") (pintype "passive"))
    )
    (net (code "11") (name "/AVDD33V") (class "Default")
      (node (ref "C60") (pin "2") (pinfunction "2_2") (pintype "passive"))
      (node (ref "C62") (pin "2") (pinfunction "2_2") (pintype "passive"))
      (node (ref "R56") (pin "2") (pinfunction "2_2") (pintype "passive"))
      (node (ref "U8") (pin "10") (pinfunction "AVDD3_10") (pintype "passive"))
      (node (ref "U8") (pin "5") (pinfunction "AVDD2_5") (pintype "passive"))
    )
    (net (code "12") (name "/CIS_BLED") (class "Default")
      (node (ref "R104") (pin "1") (pinfunction "1_1") (pintype "passive"))
      (node (ref "R108") (pin "1") (pinfunction "1_1") (pintype "passive"))
      (node (ref "U2") (pin "12") (pinfunction "CISBLED_12") (pintype "passive"))
    )
    (net (code "13") (name "/CIS_CLK") (class "Default")
      (node (ref "J1") (pin "12") (pinfunction "CIS_CLK_12") (pintype "passive"))
      (node (ref "J2") (pin "12") (pinfunction "CIS_CLK_12") (pintype "passive"))
      (node (ref "U2") (pin "8") (pinfunction "CIS_CLK_8") (pintype "passive"))
    )
    (net (code "14") (name "/CIS_GLED") (class "Default")
      (node (ref "R103") (pin "1") (pinfunction "1_1") (pintype "passive"))
      (node (ref "R105") (pin "1") (pinfunction "1_1") (pintype "passive"))
      (node (ref "U2") (pin "10") (pinfunction "CIS_GLED_10") (pintype "passive"))
    )
    (net (code "15") (name "/CIS_IRLED") (class "Default")
      (node (ref "R107") (pin "1") (pinfunction "1_1") (pintype "passive"))
      (node (ref "U2") (pin "13") (pinfunction "CIS_IRLED_13") (pintype "passive"))
    )
    (net (code "16") (name "/CIS_MODE") (class "Default")
      (node (ref "J1") (pin "8") (pinfunction "CIS_MODE_8") (pintype "passive"))
      (node (ref "J2") (pin "8") (pinfunction "CIS_MODE_8") (pintype "passive"))
      (node (ref "U2") (pin "5") (pinfunction "CIS_MODE_5") (pintype "passive"))
    )
    (net (code "17") (name "/CIS_RLED") (class "Default")
      (node (ref "R100") (pin "1") (pinfunction "1_1") (pintype "passive"))
      (node (ref "R106") (pin "1") (pinfunction "1_1") (pintype "passive"))
      (node (ref "U2") (pin "11") (pinfunction "CIS_RLED_11") (pintype "passive"))
    )
    (net (code "18") (name "/CIS_SP") (class "Default")
      (node (ref "J1") (pin "10") (pinfunction "SI_10") (pintype "passive"))
      (node (ref "J2") (pin "10") (pinfunction "SI_10") (pintype "passive"))
      (node (ref "U2") (pin "6") (pinfunction "CIS_SP_6") (pintype "passive"))
    )
    (net (code "19") (name "/CIS_UVLED") (class "Default")
      (node (ref "R101") (pin "1") (pinfunction "1_1") (pintype "passive"))
      (node (ref "U2") (pin "14") (pinfunction "CIS_UVLED_14") (pintype "passive"))
    )
    (net (code "20") (name "/DM1") (class "Default")
      (node (ref "J5") (pin "2") (pinfunction "D-_2") (pintype "passive"))
      (node (ref "U8") (pin "27") (pinfunction "DM1_27") (pintype "passive"))
    )
    (net (code "21") (name "/DM2") (class "Default")
      (node (ref "J6") (pin "2") (pinfunction "D-_2") (pintype "passive"))
      (node (ref "U8") (pin "2") (pinfunction "DM2_2") (pintype "passive"))
    )
    (net (code "22") (name "/DM3") (class "Default")
      (node (ref "J7") (pin "2") (pinfunction "D-_2") (pintype "passive"))
      (node (ref "U8") (pin "8") (pinfunction "DM3_8") (pintype "passive"))
    )
    (net (code "23") (name "/DM4") (class "Default")
      (node (ref "R66") (pin "1") (pinfunction "1_1") (pintype "passive"))
      (node (ref "U8") (pin "11") (pinfunction "DM4_11") (pintype "passive"))
    )
    (net (code "24") (name "/DP1") (class "Default")
      (node (ref "J5") (pin "3") (pinfunction "D+_3") (pintype "passive"))
      (node (ref "U8") (pin "28") (pinfunction "DP1_28") (pintype "passive"))
    )
    (net (code "25") (name "/DP2") (class "Default")
      (node (ref "J6") (pin "3") (pinfunction "D+_3") (pintype "passive"))
      (node (ref "U8") (pin "3") (pinfunction "DP2_3") (pintype "passive"))
    )
    (net (code "26") (name "/DP3") (class "Default")
      (node (ref "J7") (pin "3") (pinfunction "D+_3") (pintype "passive"))
      (node (ref "U8") (pin "9") (pinfunction "DMP3_9") (pintype "passive"))
    )
    (net (code "27") (name "/DP4") (class "Default")
      (node (ref "R68") (pin "1") (pinfunction "1_1") (pintype "passive"))
      (node (ref "U8") (pin "12") (pinfunction "DP4_12") (pintype "passive"))
    )
    (net (code "28") (name "/FRAME_START") (class "Default")
      (node (ref "J13") (pin "2") (pinfunction "2_2") (pintype "passive"))
      (node (ref "U2") (pin "40") (pinfunction "FRM_START_40") (pintype "passive"))
    )
    (net (code "29") (name "/HD_MWEN") (class "Default")
      (node (ref "U2") (pin "36") (pinfunction "HD_MWEN_36") (pintype "passive"))
      (node (ref "U4") (pin "47") (pinfunction "CSI-HSYNC_47") (pintype "passive"))
    )
    (net (code "30") (name "/HUB-RST") (class "Default")
      (node (ref "C79") (pin "2") (pinfunction "2_2") (pintype "passive"))
      (node (ref "R76") (pin "2") (pinfunction "2_2") (pintype "passive"))
      (node (ref "U8") (pin "13") (pinfunction "RESET_13") (pintype "passive"))
    )
    (net (code "31") (name "/HUB-X1") (class "Default")
      (node (ref "C63") (pin "1") (pinfunction "1_1") (pintype "passive"))
      (node (ref "U7") (pin "1") (pinfunction "X1_1") (pintype "passive"))
      (node (ref "U8") (pin "6") (pinfunction "XTAL1_6") (pintype "passive"))
    )
    (net (code "32") (name "/HUB-X2") (class "Default")
      (node (ref "C64") (pin "1") (pinfunction "1_1") (pintype "passive"))
      (node (ref "U7") (pin "3") (pinfunction "X2_3") (pintype "passive"))
      (node (ref "U8") (pin "7") (pinfunction "XTAL2_7") (pintype "passive"))
    )
    (net (code "33") (name "/HUB_V33") (class "Default")
      (node (ref "C57") (pin "2") (pinfunction "2_2") (pintype "passive"))
      (node (ref "C58") (pin "2") (pinfunction "2_2") (pintype "passive"))
      (node (ref "C59") (pin "2") (pinfunction "2_2") (pintype "passive"))
      (node (ref "C61") (pin "2") (pinfunction "2_2") (pintype "passive"))
      (node (ref "R55") (pin "1") (pinfunction "1_1") (pintype "passive"))
      (node (ref "R56") (pin "1") (pinfunction "1_1") (pintype "passive"))
      (node (ref "U5") (pin "5") (pinfunction "VOUT_5") (pintype "passive"))
      (node (ref "U8") (pin "24") (pinfunction "V33_24") (pintype "passive"))
    )
    (net (code "34") (name "/LCD-BL-EN") (class "Default")
      (node (ref "J13") (pin "5") (pinfunction "5_5") (pintype "passive"))
      (node (ref "U4") (pin "132") (pinfunction "LCD-BL-EN_132") (pintype "passive"))
    )
    (net (code "35") (name "/LCD-CLK") (class "Default")
      (node (ref "*") (pin "36") (pinfunction "36_36") (pintype "passive"))
      (node (ref "U4") (pin "80") (pinfunction "LCK-CLK_80") (pintype "passive"))
    )
    (net (code "36") (name "/LCD-D2") (class "Default")
      (node (ref "*") (pin "5") (pinfunction "5_5") (pintype "passive"))
      (node (ref "U4") (pin "99") (pinfunction "LCD-D2_99") (pintype "passive"))
    )
    (net (code "37") (name "/LCD-D3") (class "Default")
      (node (ref "*") (pin "6") (pinfunction "6_6") (pintype "passive"))
      (node (ref "U4") (pin "98") (pinfunction "LCD-D3_98") (pintype "passive"))
    )
    (net (code "38") (name "/LCD-D4") (class "Default")
      (node (ref "*") (pin "7") (pinfunction "7_7") (pintype "passive"))
      (node (ref "U4") (pin "97") (pinfunction "LCD-D4_97") (pintype "passive"))
    )
    (net (code "39") (name "/LCD-D5") (class "Default")
      (node (ref "*") (pin "8") (pinfunction "8_8") (pintype "passive"))
      (node (ref "U4") (pin "96") (pinfunction "LCD-D5_96") (pintype "passive"))
    )
    (net (code "40") (name "/LCD-D6") (class "Default")
      (node (ref "*") (pin "9") (pinfunction "9_9") (pintype "passive"))
      (node (ref "U4") (pin "95") (pinfunction "LCD-D6_95") (pintype "passive"))
    )
    (net (code "41") (name "/LCD-D7") (class "Default")
      (node (ref "*") (pin "10") (pinfunction "10_10") (pintype "passive"))
      (node (ref "U4") (pin "94") (pinfunction "LCD-D7_94") (pintype "passive"))
    )
    (net (code "42") (name "/LCD-D10") (class "Default")
      (node (ref "*") (pin "14") (pinfunction "14_14") (pintype "passive"))
      (node (ref "U4") (pin "87") (pinfunction "LCD-D10_87") (pintype "passive"))
    )
    (net (code "43") (name "/LCD-D11") (class "Default")
      (node (ref "*") (pin "15") (pinfunction "15_15") (pintype "passive"))
      (node (ref "U4") (pin "86") (pinfunction "LCD-D11_86") (pintype "passive"))
    )
    (net (code "44") (name "/LCD-D12") (class "Default")
      (node (ref "*") (pin "16") (pinfunction "16_16") (pintype "passive"))
      (node (ref "U4") (pin "85") (pinfunction "LCD-D12_85") (pintype "passive"))
    )
    (net (code "45") (name "/LCD-D13") (class "Default")
      (node (ref "*") (pin "17") (pinfunction "17_17") (pintype "passive"))
      (node (ref "U4") (pin "84") (pinfunction "LCD-D13_84") (pintype "passive"))
    )
    (net (code "46") (name "/LCD-D14") (class "Default")
      (node (ref "*") (pin "18") (pinfunction "18_18") (pintype "passive"))
      (node (ref "U4") (pin "83") (pinfunction "LCD-D14_83") (pintype "passive"))
    )
    (net (code "47") (name "/LCD-D15") (class "Default")
      (node (ref "*") (pin "19") (pinfunction "19_19") (pintype "passive"))
      (node (ref "U4") (pin "82") (pinfunction "LCD-D15_82") (pintype "passive"))
    )
    (net (code "48") (name "/LCD-D18") (class "Default")
      (node (ref "*") (pin "23") (pinfunction "23_23") (pintype "passive"))
      (node (ref "U4") (pin "93") (pinfunction "LCD-D18_93") (pintype "passive"))
    )
    (net (code "49") (name "/LCD-D19") (class "Default")
      (node (ref "*") (pin "24") (pinfunction "24_24") (pintype "passive"))
      (node (ref "U4") (pin "92") (pinfunction "LCD-D19_92") (pintype "passive"))
    )
    (net (code "50") (name "/LCD-D20") (class "Default")
      (node (ref "*") (pin "25") (pinfunction "25_25") (pintype "passive"))
      (node (ref "U4") (pin "91") (pinfunction "LCD-D20_91") (pintype "passive"))
    )
    (net (code "51") (name "/LCD-D21") (class "Default")
      (node (ref "*") (pin "26") (pinfunction "26_26") (pintype "passive"))
      (node (ref "U4") (pin "90") (pinfunction "LCD-D21_90") (pintype "passive"))
    )
    (net (code "52") (name "/LCD-D22") (class "Default")
      (node (ref "*") (pin "27") (pinfunction "27_27") (pintype "passive"))
      (node (ref "U4") (pin "89") (pinfunction "LCD-D22_89") (pintype "passive"))
    )
    (net (code "53") (name "/LCD-D23") (class "Default")
      (node (ref "*") (pin "28") (pinfunction "28_28") (pintype "passive"))
      (node (ref "U4") (pin "88") (pinfunction "LCD-D23_88") (pintype "passive"))
    )
    (net (code "54") (name "/LCD-DE") (class "Default")
      (node (ref "*") (pin "33") (pinfunction "33_33") (pintype "passive"))
      (node (ref "U4") (pin "79") (pinfunction "LCK-DE_79") (pintype "passive"))
    )
    (net (code "55") (name "/LCD-HSYNC") (class "Default")
      (node (ref "R54") (pin "1") (pinfunction "1_1") (pintype "passive"))
      (node (ref "U4") (pin "78") (pinfunction "LCK-HSYNC_78") (pintype "passive"))
    )
    (net (code "56") (name "/LCD-RST") (class "Default")
      (node (ref "J13") (pin "4") (pinfunction "4_4") (pintype "passive"))
      (node (ref "U4") (pin "131") (pinfunction "LCD-RST_131") (pintype "passive"))
    )
    (net (code "57") (name "/LCD-VSYNC") (class "Default")
      (node (ref "R53") (pin "1") (pinfunction "1_1") (pintype "passive"))
      (node (ref "U4") (pin "77") (pinfunction "LCD-VSYNC_77") (pintype "passive"))
    )
    (net (code "58") (name "/LED_BAN") (class "Default")
      (node (ref "R3") (pin "1") (pinfunction "1_1") (pintype "passive"))
      (node (ref "U1") (pin "11") (pinfunction "8C_11") (pintype "passive"))
    )
    (net (code "59") (name "/LED_BBN") (class "Default")
      (node (ref "R17") (pin "1") (pinfunction "1_1") (pintype "passive"))
      (node (ref "U1") (pin "15") (pinfunction "4C_15") (pintype "passive"))
    )
    (net (code "60") (name "/LED_GAN") (class "Default")
      (node (ref "R1") (pin "1") (pinfunction "1_1") (pintype "passive"))
      (node (ref "U1") (pin "14") (pinfunction "5C_14") (pintype "passive"))
    )
    (net (code "61") (name "/LED_GBN") (class "Default")
      (node (ref "R15") (pin "1") (pinfunction "1_1") (pintype "passive"))
      (node (ref "U1") (pin "16") (pinfunction "3C_16") (pintype "passive"))
    )
    (net (code "62") (name "/LED_IRAN") (class "Default")
      (node (ref "R4") (pin "1") (pinfunction "1_1") (pintype "passive"))
      (node (ref "U1") (pin "12") (pinfunction "7C_12") (pintype "passive"))
    )
    (net (code "63") (name "/LED_RAN") (class "Default")
      (node (ref "R2") (pin "1") (pinfunction "1_1") (pintype "passive"))
      (node (ref "U1") (pin "13") (pinfunction "6C_13") (pintype "passive"))
    )
    (net (code "64") (name "/LED_RBN") (class "Default")
      (node (ref "R16") (pin "1") (pinfunction "1_1") (pintype "passive"))
      (node (ref "U1") (pin "18") (pinfunction "1C_18") (pintype "passive"))
    )
    (net (code "65") (name "/LED_UVBN") (class "Default")
      (node (ref "J3") (pin "1") (pinfunction "1_1") (pintype "passive"))
      (node (ref "R18") (pin "1") (pinfunction "1_1") (pintype "passive"))
      (node (ref "U1") (pin "17") (pinfunction "2C_17") (pintype "passive"))
    )
    (net (code "66") (name "/MCLK") (class "Default")
      (node (ref "J13") (pin "3") (pinfunction "3_3") (pintype "passive"))
      (node (ref "U2") (pin "42") (pinfunction "ROLLER_IN_42") (pintype "passive"))
    )
    (net (code "67") (name "/NET_1V0") (class "Default")
      (node (ref "C67") (pin "1") (pinfunction "1_1") (pintype "passive"))
      (node (ref "C72") (pin "1") (pinfunction "1_1") (pintype "passive"))
      (node (ref "C73") (pin "1") (pinfunction "1_1") (pintype "passive"))
      (node (ref "U9") (pin "16") (pinfunction "DVDD10_16") (pintype "passive"))
      (node (ref "U9") (pin "23") (pinfunction "CTRL10_23") (pintype "passive"))
      (node (ref "U9") (pin "9") (pinfunction "U2VDD10_9") (pintype "passive"))
    )
    (net (code "68") (name "/NET_3V3") (class "Default")
      (node (ref "C66") (pin "2") (pinfunction "2_2") (pintype "passive"))
      (node (ref "C68") (pin "1") (pinfunction "1_1") (pintype "passive"))
      (node (ref "C71") (pin "1") (pinfunction "1_1") (pintype "passive"))
      (node (ref "D4") (pin "1") (pinfunction "A_1") (pintype "passive"))
      (node (ref "D6") (pin "1") (pinfunction "A_1") (pintype "passive"))
      (node (ref "J8") (pin "12") (pinfunction "YLED_R_12") (pintype "passive"))
      (node (ref "J8") (pin "9") (pinfunction "GLED_L_9") (pintype "passive"))
      (node (ref "R55") (pin "2") (pinfunction "2_2") (pintype "passive"))
      (node (ref "R69") (pin "1") (pinfunction "1_1") (pintype "passive"))
      (node (ref "R70") (pin "2") (pinfunction "2_2") (pintype "passive"))
      (node (ref "R72") (pin "2") (pinfunction "2_2") (pintype "passive"))
      (node (ref "U9") (pin "1") (pinfunction "HV_1") (pintype "passive"))
      (node (ref "U9") (pin "10") (pinfunction "VDD33OUT_10") (pintype "passive"))
      (node (ref "U9") (pin "13") (pinfunction "DVDD33_13") (pintype "passive"))
    )
    (net (code "69") (name "/NET_5V") (class "Default")
      (node (ref "C70") (pin "1") (pinfunction "1_1") (pintype "passive"))
      (node (ref "R65") (pin "2") (pinfunction "2_2") (pintype "passive"))
      (node (ref "U9") (pin "11") (pinfunction "VDD5IN_11") (pintype "passive"))
    )
    (net (code "70") (name "/NET_LED_LINK") (class "Default")
      (node (ref "R73") (pin "1") (pinfunction "1_1") (pintype "passive"))
      (node (ref "U9") (pin "15") (pinfunction "LEDPIN9LED0)/SPICSB_15") (pintype "passive"))
    )
    (net (code "71") (name "/NET_LED_TXRX") (class "Default")
      (node (ref "R74") (pin "1") (pinfunction "1_1") (pintype "passive"))
      (node (ref "U9") (pin "17") (pinfunction "EESKPIN9(LED1)/SPISCK_17") (pintype "passive"))
    )
    (net (code "72") (name "/NET_RXIN") (class "Default")
      (node (ref "J8") (pin "6") (pinfunction "TX-_6") (pintype "passive"))
      (node (ref "U9") (pin "5") (pinfunction "MDIN1_5") (pintype "passive"))
    )
    (net (code "73") (name "/NET_RXIP") (class "Default")
      (node (ref "J8") (pin "3") (pinfunction "TX+_3") (pintype "passive"))
      (node (ref "U9") (pin "4") (pinfunction "MDIP1_4") (pintype "passive"))
    )
    (net (code "74") (name "/NET_TXON") (class "Default")
      (node (ref "J8") (pin "2") (pinfunction "RX-_2") (pintype "passive"))
      (node (ref "U9") (pin "3") (pinfunction "MDIN0_3") (pintype "passive"))
    )
    (net (code "75") (name "/NET_TXOP") (class "Default")
      (node (ref "J8") (pin "1") (pinfunction "RX+_1") (pintype "passive"))
      (node (ref "U9") (pin "2") (pinfunction "MDIP0_2") (pintype "passive"))
    )
    (net (code "76") (name "/PCLK") (class "Default")
      (node (ref "U2") (pin "38") (pinfunction "PCLK_MWAIT_38") (pintype "passive"))
      (node (ref "U4") (pin "50") (pinfunction "CSI-PCLK_50") (pintype "passive"))
    )
    (net (code "77") (name "/RSTN") (class "Default")
      (node (ref "C24") (pin "2") (pinfunction "2_2") (pintype "passive"))
      (node (ref "C28") (pin "1") (pinfunction "1_1") (pintype "passive"))
      (node (ref "R23") (pin "1") (pinfunction "1_1") (pintype "passive"))
      (node (ref "SW1") (pin "1") (pinfunction "1_1") (pintype "passive"))
      (node (ref "U2") (pin "41") (pinfunction "RSTN_41") (pintype "passive"))
      (node (ref "U4") (pin "19") (pinfunction "RESET_19") (pintype "passive"))
    )
    (net (code "78") (name "/SPI0_CLK") (class "Default")
      (node (ref "U2") (pin "2") (pinfunction "SCK_2") (pintype "passive"))
      (node (ref "U4") (pin "9") (pinfunction "SPI0-CLK_9") (pintype "passive"))
    )
    (net (code "79") (name "/SPI0_CS") (class "Default")
      (node (ref "U2") (pin "1") (pinfunction "SCSN_1") (pintype "passive"))
      (node (ref "U4") (pin "10") (pinfunction "SPI0-CS_10") (pintype "passive"))
    )
    (net (code "80") (name "/SPI0_MISO") (class "Default")
      (node (ref "U2") (pin "4") (pinfunction "ROLLER_OUT_4") (pintype "passive"))
      (node (ref "U4") (pin "7") (pinfunction "SPI0-MISO_7") (pintype "passive"))
    )
    (net (code "81") (name "/SPI0_MOSI") (class "Default")
      (node (ref "U2") (pin "3") (pinfunction "SDIO_3") (pintype "passive"))
      (node (ref "U4") (pin "8") (pinfunction "SPI0-MOSI_8") (pintype "passive"))
    )
    (net (code "82") (name "/TP-INT") (class "Default")
      (node (ref "*") (pin "39") (pinfunction "39_39") (pintype "passive"))
      (node (ref "U4") (pin "153") (pinfunction "TP-INT_153") (pintype "passive"))
    )
    (net (code "83") (name "/TP-RST") (class "Default")
      (node (ref "*") (pin "37") (pinfunction "37_37") (pintype "passive"))
      (node (ref "*") (pin "38") (pinfunction "38_38") (pintype "passive"))
      (node (ref "U4") (pin "133") (pinfunction "TP-RST_133") (pintype "passive"))
    )
    (net (code "84") (name "/TP-SCK") (class "Default")
      (node (ref "*") (pin "32") (pinfunction "32_32") (pintype "passive"))
      (node (ref "R52") (pin "2") (pinfunction "2_2") (pintype "passive"))
      (node (ref "U4") (pin "2") (pinfunction "TP-SCK_2") (pintype "passive"))
    )
    (net (code "85") (name "/TP-SDA") (class "Default")
      (node (ref "*") (pin "31") (pinfunction "31_31") (pintype "passive"))
      (node (ref "R51") (pin "2") (pinfunction "2_2") (pintype "passive"))
      (node (ref "U4") (pin "1") (pinfunction "TP-SDA_1") (pintype "passive"))
    )
    (net (code "86") (name "/USB-DM1") (class "Default")
      (node (ref "U4") (pin "112") (pinfunction "USB-DM1_112") (pintype "passive"))
      (node (ref "U8") (pin "25") (pinfunction "DM0_25") (pintype "passive"))
    )
    (net (code "87") (name "/USB-DP1") (class "Default")
      (node (ref "U4") (pin "113") (pinfunction "USB-DP1_113") (pintype "passive"))
      (node (ref "U8") (pin "26") (pinfunction "DP0_26") (pintype "passive"))
    )
    (net (code "88") (name "/VCC_5V_UV") (class "Default")
      (node (ref "C39") (pin "1") (pinfunction "1_1") (pintype "passive"))
      (node (ref "D2") (pin "1") (pinfunction "A_1") (pintype "passive"))
      (node (ref "J21") (pin "1") (pinfunction "VCC-5V_1") (pintype "passive"))
      (node (ref "power") (pin "1") (pinfunction "1_1") (pintype "passive"))
    )
    (net (code "89") (name "/VD_MOEN") (class "Default")
      (node (ref "U2") (pin "35") (pinfunction "VD_MOEN_35") (pintype "passive"))
      (node (ref "U4") (pin "46") (pinfunction "CSI-VSYNC_46") (pintype "passive"))
    )
    (net (code "90") (name "/VIN1A") (class "Default")
      (node (ref "J1") (pin "1") (pinfunction "VIN1_1") (pintype "passive"))
      (node (ref "R10") (pin "1") (pinfunction "1_1") (pintype "passive"))
    )
    (net (code "91") (name "/VIN1B") (class "Default")
      (node (ref "J2") (pin "1") (pinfunction "VIN1_1") (pintype "passive"))
      (node (ref "R28") (pin "1") (pinfunction "1_1") (pintype "passive"))
    )
    (net (code "92") (name "/VIN1_A") (class "Default")
      (node (ref "C15") (pin "2") (pinfunction "2_2") (pintype "passive"))
      (node (ref "R10") (pin "2") (pinfunction "2_2") (pintype "passive"))
      (node (ref "U2") (pin "55") (pinfunction "VI1C_55") (pintype "passive"))
    )
    (net (code "93") (name "/VIN1_B") (class "Default")
      (node (ref "C34") (pin "2") (pinfunction "2_2") (pintype "passive"))
      (node (ref "R28") (pin "2") (pinfunction "2_2") (pintype "passive"))
      (node (ref "U2") (pin "56") (pinfunction "VI2C_56") (pintype "passive"))
    )
    (net (code "94") (name "/VIN2A") (class "Default")
      (node (ref "J1") (pin "3") (pinfunction "VIN2_3") (pintype "passive"))
      (node (ref "R11") (pin "1") (pinfunction "1_1") (pintype "passive"))
    )
    (net (code "95") (name "/VIN2B") (class "Default")
      (node (ref "J2") (pin "3") (pinfunction "VIN2_3") (pintype "passive"))
      (node (ref "R29") (pin "1") (pinfunction "1_1") (pintype "passive"))
    )
    (net (code "96") (name "/VIN2_A") (class "Default")
      (node (ref "C16") (pin "2") (pinfunction "2_2") (pintype "passive"))
      (node (ref "R11") (pin "2") (pinfunction "2_2") (pintype "passive"))
      (node (ref "U2") (pin "54") (pinfunction "VI1B_54") (pintype "passive"))
    )
    (net (code "97") (name "/VIN2_B") (class "Default")
      (node (ref "C35") (pin "2") (pinfunction "2_2") (pintype "passive"))
      (node (ref "R29") (pin "2") (pinfunction "2_2") (pintype "passive"))
      (node (ref "U2") (pin "57") (pinfunction "VI2B_57") (pintype "passive"))
    )
    (net (code "98") (name "/VIN3A") (class "Default")
      (node (ref "J1") (pin "5") (pinfunction "VIN3_5") (pintype "passive"))
      (node (ref "R12") (pin "1") (pinfunction "1_1") (pintype "passive"))
    )
    (net (code "99") (name "/VIN3B") (class "Default")
      (node (ref "J2") (pin "5") (pinfunction "VIN3_5") (pintype "passive"))
      (node (ref "R30") (pin "1") (pinfunction "1_1") (pintype "passive"))
    )
    (net (code "100") (name "/VIN3_A") (class "Default")
      (node (ref "C17") (pin "2") (pinfunction "2_2") (pintype "passive"))
      (node (ref "R12") (pin "2") (pinfunction "2_2") (pintype "passive"))
      (node (ref "U2") (pin "53") (pinfunction "VI1A_53") (pintype "passive"))
    )
    (net (code "101") (name "/VIN3_B") (class "Default")
      (node (ref "C36") (pin "2") (pinfunction "2_2") (pintype "passive"))
      (node (ref "R30") (pin "2") (pinfunction "2_2") (pintype "passive"))
      (node (ref "U2") (pin "58") (pinfunction "VI2A_58") (pintype "passive"))
    )
    (net (code "102") (name "/VREFA") (class "Default")
      (node (ref "J1") (pin "7") (pinfunction "VREF_7") (pintype "passive"))
      (node (ref "R9") (pin "1") (pinfunction "1_1") (pintype "passive"))
    )
    (net (code "103") (name "/VREFB") (class "Default")
      (node (ref "J2") (pin "7") (pinfunction "VREF_7") (pintype "passive"))
      (node (ref "R13") (pin "1") (pinfunction "1_1") (pintype "passive"))
    )
    (net (code "104") (name "DC-5V") (class "Default")
      (node (ref "B1") (pin "1") (pinfunction "1_1") (pintype "passive"))
      (node (ref "C1") (pin "2") (pinfunction "2_2") (pintype "passive"))
      (node (ref "C2") (pin "2") (pinfunction "2_2") (pintype "passive"))
      (node (ref "C37") (pin "1") (pinfunction "1_1") (pintype "passive"))
      (node (ref "C38") (pin "2") (pinfunction "2_2") (pintype "passive"))
      (node (ref "C42") (pin "2") (pinfunction "2_2") (pintype "passive"))
      (node (ref "C51") (pin "1") (pinfunction "1_1") (pintype "passive"))
      (node (ref "C52") (pin "1") (pinfunction "1_1") (pintype "passive"))
      (node (ref "C56") (pin "2") (pinfunction "2_2") (pintype "passive"))
      (node (ref "C65") (pin "1") (pinfunction "1_1") (pintype "passive"))
      (node (ref "C77") (pin "1") (pinfunction "1_1") (pintype "passive"))
      (node (ref "C78") (pin "1") (pinfunction "1_1") (pintype "passive"))
      (node (ref "D1") (pin "1") (pinfunction "A_1") (pintype "passive"))
      (node (ref "D11") (pin "2") (pinfunction "K_2") (pintype "passive"))
      (node (ref "D2") (pin "2") (pinfunction "K_2") (pintype "passive"))
      (node (ref "J1") (pin "13") (pinfunction "VCC_5V_13") (pintype "passive"))
      (node (ref "J2") (pin "13") (pinfunction "VCC_5V_13") (pintype "passive"))
      (node (ref "J5") (pin "1") (pinfunction "VBUS_1") (pintype "passive"))
      (node (ref "J6") (pin "1") (pinfunction "VBUS_1") (pintype "passive"))
      (node (ref "J7") (pin "1") (pinfunction "VBUS_1") (pintype "passive"))
      (node (ref "LD1117AG-33") (pin "3") (pinfunction "VIN_3") (pintype "passive"))
      (node (ref "LD1117AG-33-AA3-A-R") (pin "3") (pinfunction "VIN_3") (pintype "passive"))
      (node (ref "R59") (pin "2") (pinfunction "2_2") (pintype "passive"))
      (node (ref "R62") (pin "2") (pinfunction "2_2") (pintype "passive"))
      (node (ref "R63") (pin "2") (pinfunction "2_2") (pintype "passive"))
      (node (ref "R65") (pin "1") (pinfunction "1_1") (pintype "passive"))
      (node (ref "R67") (pin "1") (pinfunction "1_1") (pintype "passive"))
      (node (ref "U1") (pin "10") (pinfunction "COM_10") (pintype "passive"))
      (node (ref "U4") (pin "26") (pinfunction "DC-5V_26") (pintype "passive"))
      (node (ref "U5") (pin "1") (pinfunction "VIN_1") (pintype "passive"))
    )
    (net (code "105") (name "GND") (class "Default")
      (node (ref "*") (pin "11") (pinfunction "11_11") (pintype "passive"))
      (node (ref "*") (pin "20") (pinfunction "20_20") (pintype "passive"))
      (node (ref "*") (pin "29") (pinfunction "29_29") (pintype "passive"))
      (node (ref "*") (pin "41") (pinfunction "41_41") (pintype "passive"))
      (node (ref "*") (pin "42") (pinfunction "42_42") (pintype "passive"))
      (node (ref "C1") (pin "1") (pinfunction "1_1") (pintype "passive"))
      (node (ref "C10") (pin "2") (pinfunction "2_2") (pintype "passive"))
      (node (ref "C13") (pin "2") (pinfunction "2_2") (pintype "passive"))
      (node (ref "C14") (pin "2") (pinfunction "2_2") (pintype "passive"))
      (node (ref "C15") (pin "1") (pinfunction "1_1") (pintype "passive"))
      (node (ref "C16") (pin "1") (pinfunction "1_1") (pintype "passive"))
      (node (ref "C17") (pin "1") (pinfunction "1_1") (pintype "passive"))
      (node (ref "C18") (pin "2") (pinfunction "2_2") (pintype "passive"))
      (node (ref "C19") (pin "1") (pinfunction "1_1") (pintype "passive"))
      (node (ref "C2") (pin "1") (pinfunction "1_1") (pintype "passive"))
      (node (ref "C20") (pin "1") (pinfunction "1_1") (pintype "passive"))
      (node (ref "C21") (pin "1") (pinfunction "1_1") (pintype "passive"))
      (node (ref "C22") (pin "1") (pinfunction "1_1") (pintype "passive"))
      (node (ref "C23") (pin "1") (pinfunction "1_1") (pintype "passive"))
      (node (ref "C24") (pin "1") (pinfunction "1_1") (pintype "passive"))
      (node (ref "C28") (pin "2") (pinfunction "2_2") (pintype "passive"))
      (node (ref "C29") (pin "1") (pinfunction "1_1") (pintype "passive"))
      (node (ref "C3") (pin "1") (pinfunction "1_1") (pintype "passive"))
      (node (ref "C30") (pin "2") (pinfunction "2_2") (pintype "passive"))
      (node (ref "C31") (pin "2") (pinfunction "2_2") (pintype "passive"))
      (node (ref "C32") (pin "1") (pinfunction "1_1") (pintype "passive"))
      (node (ref "C33") (pin "1") (pinfunction "1_1") (pintype "passive"))
      (node (ref "C34") (pin "1") (pinfunction "1_1") (pintype "passive"))
      (node (ref "C35") (pin "1") (pinfunction "1_1") (pintype "passive"))
      (node (ref "C36") (pin "1") (pinfunction "1_1") (pintype "passive"))
      (node (ref "C37") (pin "2") (pinfunction "2_2") (pintype "passive"))
      (node (ref "C38") (pin "1") (pinfunction "1_1") (pintype "passive"))
      (node (ref "C39") (pin "2") (pinfunction "2_2") (pintype "passive"))
      (node (ref "C4") (pin "1") (pinfunction "1_1") (pintype "passive"))
      (node (ref "C40") (pin "2") (pinfunction "2_2") (pintype "passive"))
      (node (ref "C41") (pin "1") (pinfunction "1_1") (pintype "passive"))
      (node (ref "C42") (pin "1") (pinfunction "1_1") (pintype "passive"))
      (node (ref "C43") (pin "2") (pinfunction "2_2") (pintype "passive"))
      (node (ref "C44") (pin "1") (pinfunction "1_1") (pintype "passive"))
      (node (ref "C45") (pin "1") (pinfunction "1_1") (pintype "passive"))
      (node (ref "C46") (pin "1") (pinfunction "1_1") (pintype "passive"))
      (node (ref "C47") (pin "1") (pinfunction "1_1") (pintype "passive"))
      (node (ref "C48") (pin "1") (pinfunction "1_1") (pintype "passive"))
      (node (ref "C5") (pin "1") (pinfunction "1_1") (pintype "passive"))
      (node (ref "C51") (pin "2") (pinfunction "2_2") (pintype "passive"))
      (node (ref "C52") (pin "2") (pinfunction "2_2") (pintype "passive"))
      (node (ref "C55") (pin "2") (pinfunction "2_2") (pintype "passive"))
      (node (ref "C56") (pin "1") (pinfunction "1_1") (pintype "passive"))
      (node (ref "C57") (pin "1") (pinfunction "1_1") (pintype "passive"))
      (node (ref "C58") (pin "1") (pinfunction "1_1") (pintype "passive"))
      (node (ref "C59") (pin "1") (pinfunction "1_1") (pintype "passive"))
      (node (ref "C6") (pin "2") (pinfunction "2_2") (pintype "passive"))
      (node (ref "C60") (pin "1") (pinfunction "1_1") (pintype "passive"))
      (node (ref "C61") (pin "1") (pinfunction "1_1") (pintype "passive"))
      (node (ref "C62") (pin "1") (pinfunction "1_1") (pintype "passive"))
      (node (ref "C63") (pin "2") (pinfunction "2_2") (pintype "passive"))
      (node (ref "C64") (pin "2") (pinfunction "2_2") (pintype "passive"))
      (node (ref "C65") (pin "2") (pinfunction "2_2") (pintype "passive"))
      (node (ref "C66") (pin "1") (pinfunction "1_1") (pintype "passive"))
      (node (ref "C67") (pin "2") (pinfunction "2_2") (pintype "passive"))
      (node (ref "C68") (pin "2") (pinfunction "2_2") (pintype "passive"))
      (node (ref "C69") (pin "2") (pinfunction "2_2") (pintype "passive"))
      (node (ref "C70") (pin "2") (pinfunction "2_2") (pintype "passive"))
      (node (ref "C71") (pin "2") (pinfunction "2_2") (pintype "passive"))
      (node (ref "C72") (pin "2") (pinfunction "2_2") (pintype "passive"))
      (node (ref "C73") (pin "2") (pinfunction "2_2") (pintype "passive"))
      (node (ref "C74") (pin "2") (pinfunction "2_2") (pintype "passive"))
      (node (ref "C75") (pin "2") (pinfunction "2_2") (pintype "passive"))
      (node (ref "C76") (pin "2") (pinfunction "2_2") (pintype "passive"))
      (node (ref "C77") (pin "2") (pinfunction "2_2") (pintype "passive"))
      (node (ref "C78") (pin "2") (pinfunction "2_2") (pintype "passive"))
      (node (ref "C79") (pin "1") (pinfunction "1_1") (pintype "passive"))
      (node (ref "C9") (pin "2") (pinfunction "2_2") (pintype "passive"))
      (node (ref "D11") (pin "1") (pinfunction "A_1") (pintype "passive"))
      (node (ref "D4") (pin "3") (pinfunction "K_3") (pintype "passive"))
      (node (ref "D5") (pin "3") (pinfunction "K_3") (pintype "passive"))
      (node (ref "D6") (pin "3") (pinfunction "K_3") (pintype "passive"))
      (node (ref "D7") (pin "3") (pinfunction "K_3") (pintype "passive"))
      (node (ref "D8") (pin "3") (pinfunction "K_3") (pintype "passive"))
      (node (ref "J1") (pin "11") (pinfunction "GND_11") (pintype "passive"))
      (node (ref "J1") (pin "2") (pinfunction "GND_2") (pintype "passive"))
      (node (ref "J1") (pin "4") (pinfunction "GND_4") (pintype "passive"))
      (node (ref "J12") (pin "1") (pinfunction "1_1") (pintype "passive"))
      (node (ref "J13") (pin "1") (pinfunction "1_1") (pintype "passive"))
      (node (ref "J2") (pin "11") (pinfunction "GND_11") (pintype "passive"))
      (node (ref "J2") (pin "2") (pinfunction "GND_2") (pintype "passive"))
      (node (ref "J2") (pin "4") (pinfunction "GND_4") (pintype "passive"))
      (node (ref "J21") (pin "2") (pinfunction "GND_2") (pintype "passive"))
      (node (ref "J21") (pin "3") (pinfunction "GND_3") (pintype "passive"))
      (node (ref "J3") (pin "2") (pinfunction "2_2") (pintype "passive"))
      (node (ref "J5") (pin "4") (pinfunction "GND_4") (pintype "passive"))
      (node (ref "J5") (pin "5") (pinfunction "GND_5") (pintype "passive"))
      (node (ref "J5") (pin "6") (pinfunction "GND_6") (pintype "passive"))
      (node (ref "J5") (pin "7") (pinfunction "GND_7") (pintype "passive"))
      (node (ref "J5") (pin "8") (pinfunction "GND_8") (pintype "passive"))
      (node (ref "J6") (pin "4") (pinfunction "GND_4") (pintype "passive"))
      (node (ref "J6") (pin "5") (pinfunction "GND_5") (pintype "passive"))
      (node (ref "J6") (pin "6") (pinfunction "GND_6") (pintype "passive"))
      (node (ref "J6") (pin "7") (pinfunction "GND_7") (pintype "passive"))
      (node (ref "J6") (pin "8") (pinfunction "GND_8") (pintype "passive"))
      (node (ref "J7") (pin "4") (pinfunction "GND_4") (pintype "passive"))
      (node (ref "J7") (pin "5") (pinfunction "GND_5") (pintype "passive"))
      (node (ref "J7") (pin "6") (pinfunction "GND_6") (pintype "passive"))
      (node (ref "J7") (pin "7") (pinfunction "GND_7") (pintype "passive"))
      (node (ref "J7") (pin "8") (pinfunction "GND_8") (pintype "passive"))
      (node (ref "J8") (pin "8") (pinfunction "N/C_8") (pintype "passive"))
      (node (ref "LD1117AG-33") (pin "1") (pinfunction "GND_1") (pintype "passive"))
      (node (ref "LD1117AG-33-AA3-A-R") (pin "1") (pinfunction "GND_1") (pintype "passive"))
      (node (ref "R34") (pin "2") (pinfunction "2_2") (pintype "passive"))
      (node (ref "R57") (pin "2") (pinfunction "2_2") (pintype "passive"))
      (node (ref "R58") (pin "1") (pinfunction "1_1") (pintype "passive"))
      (node (ref "R64") (pin "1") (pinfunction "1_1") (pintype "passive"))
      (node (ref "R67") (pin "2") (pinfunction "2_2") (pintype "passive"))
      (node (ref "R71") (pin "2") (pinfunction "2_2") (pintype "passive"))
      (node (ref "R75") (pin "2") (pinfunction "2_2") (pintype "passive"))
      (node (ref "SW1") (pin "2") (pinfunction "2_2") (pintype "passive"))
      (node (ref "U1") (pin "9") (pinfunction "GND_9") (pintype "passive"))
      (node (ref "U10") (pin "2") (pinfunction "GND_2") (pintype "passive"))
      (node (ref "U2") (pin "26") (pinfunction "PVSS_26") (pintype "passive"))
      (node (ref "U2") (pin "39") (pinfunction "PVSS_39") (pintype "passive"))
      (node (ref "U2") (pin "43") (pinfunction "DVSS_43") (pintype "passive"))
      (node (ref "U2") (pin "46") (pinfunction "AVSS_46") (pintype "passive"))
      (node (ref "U2") (pin "47") (pinfunction "AVSS1_47") (pintype "passive"))
      (node (ref "U2") (pin "51") (pinfunction "AVSS1_51") (pintype "passive"))
      (node (ref "U2") (pin "60") (pinfunction "AVSS2_60") (pintype "passive"))
      (node (ref "U2") (pin "64") (pinfunction "AVSS2_64") (pintype "passive"))
      (node (ref "U2") (pin "9") (pinfunction "PVSS_9") (pintype "passive"))
      (node (ref "U4") (pin "111") (pinfunction "GND_111") (pintype "passive"))
      (node (ref "U4") (pin "114") (pinfunction "GND_114") (pintype "passive"))
      (node (ref "U4") (pin "117") (pinfunction "GND_117") (pintype "passive"))
      (node (ref "U4") (pin "20") (pinfunction "GND_20") (pintype "passive"))
      (node (ref "U4") (pin "32") (pinfunction "GND_32") (pintype "passive"))
      (node (ref "U4") (pin "33") (pinfunction "GND_33") (pintype "passive"))
      (node (ref "U4") (pin "34") (pinfunction "GND_34") (pintype "passive"))
      (node (ref "U4") (pin "35") (pinfunction "GND_35") (pintype "passive"))
      (node (ref "U4") (pin "36") (pinfunction "GND_36") (pintype "passive"))
      (node (ref "U4") (pin "49") (pinfunction "GND_49") (pintype "passive"))
      (node (ref "U4") (pin "65") (pinfunction "GND_65") (pintype "passive"))
      (node (ref "U4") (pin "76") (pinfunction "GND_76") (pintype "passive"))
      (node (ref "U4") (pin "81") (pinfunction "GND_81") (pintype "passive"))
      (node (ref "U5") (pin "2") (pinfunction "GND_2") (pintype "passive"))
      (node (ref "U5") (pin "3") (pinfunction "EN_3") (pintype "passive"))
      (node (ref "U7") (pin "2") (pinfunction "GND_2") (pintype "passive"))
      (node (ref "U8") (pin "15") (pinfunction "GND_15") (pintype "passive"))
      (node (ref "U9") (pin "25") (pinfunction "GND1_25") (pintype "passive"))
      (node (ref "U9") (pin "26") (pinfunction "GND2_26") (pintype "passive"))
      (node (ref "U9") (pin "27") (pinfunction "GND3_27") (pintype "passive"))
      (node (ref "U9") (pin "28") (pinfunction "GND4_28") (pintype "passive"))
      (node (ref "U9") (pin "6") (pinfunction "U2GND_6") (pintype "passive"))
      (node (ref "power") (pin "2") (pinfunction "2_2") (pintype "passive"))
    )
    (net (code "106") (name "HUB-V33") (class "Default")
      (node (ref "R60") (pin "2") (pinfunction "2_2") (pintype "passive"))
      (node (ref "R61") (pin "2") (pinfunction "2_2") (pintype "passive"))
      (node (ref "R76") (pin "1") (pinfunction "1_1") (pintype "passive"))
      (node (ref "U8") (pin "1") (pinfunction "AVDD1_1") (pintype "passive"))
      (node (ref "U8") (pin "16") (pinfunction "DVDD_16") (pintype "passive"))
    )
    (net (code "107") (name "Net-(*-Pad1)") (class "Default")
      (node (ref "*") (pin "1") (pinfunction "1_1") (pintype "passive"))
      (node (ref "*") (pin "2") (pinfunction "2_2") (pintype "passive"))
      (node (ref "B1") (pin "2") (pinfunction "2_2") (pintype "passive"))
      (node (ref "C55") (pin "1") (pinfunction "1_1") (pintype "passive"))
    )
    (net (code "108") (name "Net-(*-Pad30)") (class "Default")
      (node (ref "*") (pin "30") (pinfunction "30_30") (pintype "passive"))
      (node (ref "R50") (pin "2") (pinfunction "2_2") (pintype "passive"))
    )
    (net (code "109") (name "Net-(*-Pad34)") (class "Default")
      (node (ref "*") (pin "34") (pinfunction "34_34") (pintype "passive"))
      (node (ref "R53") (pin "2") (pinfunction "2_2") (pintype "passive"))
    )
    (net (code "110") (name "Net-(*-Pad35)") (class "Default")
      (node (ref "*") (pin "35") (pinfunction "35_35") (pintype "passive"))
      (node (ref "R54") (pin "2") (pinfunction "2_2") (pintype "passive"))
    )
    (net (code "111") (name "Net-(D1-K)") (class "Default")
      (node (ref "D1") (pin "2") (pinfunction "K_2") (pintype "passive"))
      (node (ref "R34") (pin "1") (pinfunction "1_1") (pintype "passive"))
    )
    (net (code "112") (name "Net-(D5-A)") (class "Default")
      (node (ref "D5") (pin "1") (pinfunction "A_1") (pintype "passive"))
      (node (ref "J8") (pin "10") (pinfunction "GLED_R_10") (pintype "passive"))
      (node (ref "R74") (pin "2") (pinfunction "2_2") (pintype "passive"))
    )
    (net (code "113") (name "Net-(D7-A)") (class "Default")
      (node (ref "D7") (pin "1") (pinfunction "A_1") (pintype "passive"))
      (node (ref "J12") (pin "2") (pinfunction "2_2") (pintype "passive"))
      (node (ref "R79") (pin "2") (pinfunction "2_2") (pintype "passive"))
    )
    (net (code "114") (name "Net-(D8-A)") (class "Default")
      (node (ref "D8") (pin "1") (pinfunction "A_1") (pintype "passive"))
      (node (ref "J12") (pin "3") (pinfunction "3_3") (pintype "passive"))
      (node (ref "R78") (pin "2") (pinfunction "2_2") (pintype "passive"))
    )
    (net (code "115") (name "Net-(J1-LED_B)") (class "Default")
      (node (ref "J1") (pin "16") (pinfunction "LED_B_16") (pintype "passive"))
      (node (ref "R3") (pin "2") (pinfunction "2_2") (pintype "passive"))
    )
    (net (code "116") (name "Net-(J1-LED_G)") (class "Default")
      (node (ref "J1") (pin "14") (pinfunction "LED_G_14") (pintype "passive"))
      (node (ref "R1") (pin "2") (pinfunction "2_2") (pintype "passive"))
    )
    (net (code "117") (name "Net-(J1-LED_IR)") (class "Default")
      (node (ref "J1") (pin "17") (pinfunction "LED_IR_17") (pintype "passive"))
      (node (ref "R4") (pin "2") (pinfunction "2_2") (pintype "passive"))
    )
    (net (code "118") (name "Net-(J1-LED_R)") (class "Default")
      (node (ref "J1") (pin "15") (pinfunction "LED_R_15") (pintype "passive"))
      (node (ref "R2") (pin "2") (pinfunction "2_2") (pintype "passive"))
    )
    (net (code "119") (name "Net-(J2-LED_B)") (class "Default")
      (node (ref "J2") (pin "16") (pinfunction "LED_B_16") (pintype "passive"))
      (node (ref "R17") (pin "2") (pinfunction "2_2") (pintype "passive"))
    )
    (net (code "120") (name "Net-(J2-LED_G)") (class "Default")
      (node (ref "J2") (pin "14") (pinfunction "LED_G_14") (pintype "passive"))
      (node (ref "R15") (pin "2") (pinfunction "2_2") (pintype "passive"))
    )
    (net (code "121") (name "Net-(J2-LED_IR)") (class "Default")
      (node (ref "J2") (pin "17") (pinfunction "LED_IR_17") (pintype "passive"))
      (node (ref "R18") (pin "2") (pinfunction "2_2") (pintype "passive"))
    )
    (net (code "122") (name "Net-(J2-LED_R)") (class "Default")
      (node (ref "J2") (pin "15") (pinfunction "LED_R_15") (pintype "passive"))
      (node (ref "R16") (pin "2") (pinfunction "2_2") (pintype "passive"))
    )
    (net (code "123") (name "Net-(J8-SHIELD1)") (class "Default")
      (node (ref "C76") (pin "1") (pinfunction "1_1") (pintype "passive"))
      (node (ref "J8") (pin "13") (pinfunction "SHIELD1_13") (pintype "passive"))
      (node (ref "J8") (pin "14") (pinfunction "SHIELD2_14") (pintype "passive"))
      (node (ref "R75") (pin "1") (pinfunction "1_1") (pintype "passive"))
    )
    (net (code "124") (name "Net-(J8-YLED_L)") (class "Default")
      (node (ref "J8") (pin "11") (pinfunction "YLED_L_11") (pintype "passive"))
      (node (ref "R73") (pin "2") (pinfunction "2_2") (pintype "passive"))
    )
    (net (code "125") (name "Net-(U1-1B)") (class "Default")
      (node (ref "R100") (pin "2") (pinfunction "2_2") (pintype "passive"))
      (node (ref "U1") (pin "1") (pinfunction "1B_1") (pintype "passive"))
    )
    (net (code "126") (name "Net-(U1-2B)") (class "Default")
      (node (ref "R101") (pin "2") (pinfunction "2_2") (pintype "passive"))
      (node (ref "U1") (pin "2") (pinfunction "2B_2") (pintype "passive"))
    )
    (net (code "127") (name "Net-(U1-3B)") (class "Default")
      (node (ref "R103") (pin "2") (pinfunction "2_2") (pintype "passive"))
      (node (ref "U1") (pin "3") (pinfunction "3B_3") (pintype "passive"))
    )
    (net (code "128") (name "Net-(U1-4B)") (class "Default")
      (node (ref "R104") (pin "2") (pinfunction "2_2") (pintype "passive"))
      (node (ref "U1") (pin "4") (pinfunction "4B_4") (pintype "passive"))
    )
    (net (code "129") (name "Net-(U1-5B)") (class "Default")
      (node (ref "R105") (pin "2") (pinfunction "2_2") (pintype "passive"))
      (node (ref "U1") (pin "5") (pinfunction "5B_5") (pintype "passive"))
    )
    (net (code "130") (name "Net-(U1-6B)") (class "Default")
      (node (ref "R106") (pin "2") (pinfunction "2_2") (pintype "passive"))
      (node (ref "U1") (pin "6") (pinfunction "6B_6") (pintype "passive"))
    )
    (net (code "131") (name "Net-(U1-7B)") (class "Default")
      (node (ref "R107") (pin "2") (pinfunction "2_2") (pintype "passive"))
      (node (ref "U1") (pin "7") (pinfunction "7B_7") (pintype "passive"))
    )
    (net (code "132") (name "Net-(U1-8B)") (class "Default")
      (node (ref "R108") (pin "2") (pinfunction "2_2") (pintype "passive"))
      (node (ref "U1") (pin "8") (pinfunction "8B_8") (pintype "passive"))
    )
    (net (code "133") (name "Net-(U2-AVDD1)") (class "Default")
      (node (ref "C19") (pin "2") (pinfunction "2_2") (pintype "passive"))
      (node (ref "C20") (pin "2") (pinfunction "2_2") (pintype "passive"))
      (node (ref "L2") (pin "2") (pinfunction "2_2") (pintype "passive"))
      (node (ref "U2") (pin "50") (pinfunction "AVDD1_50") (pintype "passive"))
    )
    (net (code "134") (name "Net-(U2-AVDD2)") (class "Default")
      (node (ref "C21") (pin "2") (pinfunction "2_2") (pintype "passive"))
      (node (ref "C22") (pin "2") (pinfunction "2_2") (pintype "passive"))
      (node (ref "L3") (pin "2") (pinfunction "2_2") (pintype "passive"))
      (node (ref "U2") (pin "61") (pinfunction "AVDD2_61") (pintype "passive"))
    )
    (net (code "135") (name "Net-(U2-BIAS1)") (class "Default")
      (node (ref "C14") (pin "1") (pinfunction "1_1") (pintype "passive"))
      (node (ref "R9") (pin "2") (pinfunction "2_2") (pintype "passive"))
      (node (ref "U2") (pin "52") (pinfunction "BIAS1_52") (pintype "passive"))
    )
    (net (code "136") (name "Net-(U2-BIAS2)") (class "Default")
      (node (ref "C18") (pin "1") (pinfunction "1_1") (pintype "passive"))
      (node (ref "R13") (pin "2") (pinfunction "2_2") (pintype "passive"))
      (node (ref "U2") (pin "59") (pinfunction "BIAS2_59") (pintype "passive"))
    )
    (net (code "137") (name "Net-(U2-REFB1)") (class "Default")
      (node (ref "C6") (pin "1") (pinfunction "1_1") (pintype "passive"))
      (node (ref "C7") (pin "2") (pinfunction "2_2") (pintype "passive"))
      (node (ref "C8") (pin "1") (pinfunction "1_1") (pintype "passive"))
      (node (ref "U2") (pin "48") (pinfunction "REFB1_48") (pintype "passive"))
    )
    (net (code "138") (name "Net-(U2-REFB2)") (class "Default")
      (node (ref "C11") (pin "1") (pinfunction "1_1") (pintype "passive"))
      (node (ref "C12") (pin "2") (pinfunction "2_2") (pintype "passive"))
      (node (ref "C13") (pin "1") (pinfunction "1_1") (pintype "passive"))
      (node (ref "U2") (pin "63") (pinfunction "REFB2_63") (pintype "passive"))
    )
    (net (code "139") (name "Net-(U2-REFT1)") (class "Default")
      (node (ref "C7") (pin "1") (pinfunction "1_1") (pintype "passive"))
      (node (ref "C8") (pin "2") (pinfunction "2_2") (pintype "passive"))
      (node (ref "C9") (pin "1") (pinfunction "1_1") (pintype "passive"))
      (node (ref "U2") (pin "49") (pinfunction "REFT1_49") (pintype "passive"))
    )
    (net (code "140") (name "Net-(U2-REFT2)") (class "Default")
      (node (ref "C10") (pin "1") (pinfunction "1_1") (pintype "passive"))
      (node (ref "C11") (pin "2") (pinfunction "2_2") (pintype "passive"))
      (node (ref "C12") (pin "1") (pinfunction "1_1") (pintype "passive"))
      (node (ref "U2") (pin "62") (pinfunction "REFT2_62") (pintype "passive"))
    )
    (net (code "141") (name "Net-(U2-V18_FLT)") (class "Default")
      (node (ref "C23") (pin "2") (pinfunction "2_2") (pintype "passive"))
      (node (ref "U2") (pin "44") (pinfunction "V18_FLT_44") (pintype "passive"))
    )
    (net (code "142") (name "Net-(U2-XIN)") (class "Default")
      (node (ref "C32") (pin "2") (pinfunction "2_2") (pintype "passive"))
      (node (ref "R27") (pin "1") (pinfunction "1_1") (pintype "passive"))
      (node (ref "U2") (pin "33") (pinfunction "XIN_33") (pintype "passive"))
      (node (ref "Y1") (pin "1") (pinfunction "OSC1_1") (pintype "passive"))
    )
    (net (code "143") (name "Net-(U2-XOUT)") (class "Default")
      (node (ref "C33") (pin "2") (pinfunction "2_2") (pintype "passive"))
      (node (ref "R27") (pin "2") (pinfunction "2_2") (pintype "passive"))
      (node (ref "U2") (pin "34") (pinfunction "XOUT_34") (pintype "passive"))
      (node (ref "Y1") (pin "2") (pinfunction "OSC2_2") (pintype "passive"))
    )
    (net (code "144") (name "Net-(U8-OVCRU1)") (class "Default")
      (node (ref "R63") (pin "1") (pinfunction "1_1") (pintype "passive"))
      (node (ref "R64") (pin "2") (pinfunction "2_2") (pintype "passive"))
      (node (ref "U8") (pin "21") (pinfunction "OVCRU1_21") (pintype "passive"))
    )
    (net (code "145") (name "Net-(U8-PGANG)") (class "Default")
      (node (ref "R61") (pin "1") (pinfunction "1_1") (pintype "passive"))
      (node (ref "U8") (pin "18") (pinfunction "PGANG_18") (pintype "passive"))
    )
    (net (code "146") (name "Net-(U8-PSELF)") (class "Default")
      (node (ref "R62") (pin "1") (pinfunction "1_1") (pintype "passive"))
      (node (ref "U8") (pin "17") (pinfunction "PSELF_17") (pintype "passive"))
    )
    (net (code "147") (name "Net-(U8-PWREN1)") (class "Default")
      (node (ref "R60") (pin "1") (pinfunction "1_1") (pintype "passive"))
      (node (ref "U8") (pin "22") (pinfunction "PWREN1_22") (pintype "passive"))
    )
    (net (code "148") (name "Net-(U8-RREF)") (class "Default")
      (node (ref "R58") (pin "2") (pinfunction "2_2") (pintype "passive"))
      (node (ref "U8") (pin "4") (pinfunction "RREF_4") (pintype "passive"))
    )
    (net (code "149") (name "Net-(U8-TEST)") (class "Default")
      (node (ref "R57") (pin "1") (pinfunction "1_1") (pintype "passive"))
      (node (ref "U8") (pin "14") (pinfunction "TEST_14") (pintype "passive"))
    )
    (net (code "150") (name "Net-(U8-V5)") (class "Default")
      (node (ref "R59") (pin "1") (pinfunction "1_1") (pintype "passive"))
      (node (ref "U8") (pin "23") (pinfunction "V5_23") (pintype "passive"))
    )
    (net (code "151") (name "Net-(U9-DVDD10_UPS)") (class "Default")
      (node (ref "C69") (pin "1") (pinfunction "1_1") (pintype "passive"))
      (node (ref "U9") (pin "12") (pinfunction "DVDD10_UPS_12") (pintype "passive"))
    )
    (net (code "152") (name "Net-(U9-EEDIPIN{slash}SPISDI{slash}XTALDET)") (class "Default")
      (node (ref "R70") (pin "1") (pinfunction "1_1") (pintype "passive"))
      (node (ref "U9") (pin "18") (pinfunction "EEDIPIN/SPISDI/XTALDET_18") (pintype "passive"))
    )
    (net (code "153") (name "Net-(U9-GPIOPIN)") (class "Default")
      (node (ref "R69") (pin "2") (pinfunction "2_2") (pintype "passive"))
      (node (ref "U9") (pin "14") (pinfunction "GPIOPIN_14") (pintype "passive"))
    )
    (net (code "154") (name "Net-(U9-LANWAKEBPIN)") (class "Default")
      (node (ref "R72") (pin "1") (pinfunction "1_1") (pintype "passive"))
      (node (ref "U9") (pin "19") (pinfunction "LANWAKEBPIN_19") (pintype "passive"))
    )
    (net (code "155") (name "Net-(U9-RSET)") (class "Default")
      (node (ref "R71") (pin "1") (pinfunction "1_1") (pintype "passive"))
      (node (ref "U9") (pin "24") (pinfunction "RSET_24") (pintype "passive"))
    )
    (net (code "156") (name "Net-(U9-U2DM)") (class "Default")
      (node (ref "R66") (pin "2") (pinfunction "2_2") (pintype "passive"))
      (node (ref "U9") (pin "7") (pinfunction "U2DM_7") (pintype "passive"))
    )
    (net (code "157") (name "Net-(U9-U2DP)") (class "Default")
      (node (ref "R68") (pin "2") (pinfunction "2_2") (pintype "passive"))
      (node (ref "U9") (pin "8") (pinfunction "U2DP_8") (pintype "passive"))
    )
    (net (code "158") (name "Net-(U10-X1)") (class "Default")
      (node (ref "C75") (pin "1") (pinfunction "1_1") (pintype "passive"))
      (node (ref "U10") (pin "1") (pinfunction "X1_1") (pintype "passive"))
      (node (ref "U9") (pin "20") (pinfunction "EEDOPIN/SPISDO_20") (pintype "passive"))
    )
    (net (code "159") (name "Net-(U10-X2)") (class "Default")
      (node (ref "C74") (pin "1") (pinfunction "1_1") (pintype "passive"))
      (node (ref "U10") (pin "3") (pinfunction "X2_3") (pintype "passive"))
      (node (ref "U9") (pin "22") (pinfunction "CKXTAL2_22") (pintype "passive"))
    )
    (net (code "160") (name "PVDDREG_3V3") (class "Default")
      (node (ref "C29") (pin "2") (pinfunction "2_2") (pintype "passive"))
      (node (ref "C30") (pin "1") (pinfunction "1_1") (pintype "passive"))
      (node (ref "C31") (pin "1") (pinfunction "1_1") (pintype "passive"))
      (node (ref "U2") (pin "45") (pinfunction "PVDDREG_45") (pintype "passive"))
    )
    (net (code "161") (name "PVDD_3V3") (class "Default")
      (node (ref "R23") (pin "2") (pinfunction "2_2") (pintype "passive"))
      (node (ref "U2") (pin "23") (pinfunction "PVDD_23") (pintype "passive"))
      (node (ref "U2") (pin "37") (pinfunction "PVDD_37") (pintype "passive"))
      (node (ref "U2") (pin "7") (pinfunction "PVDD_7") (pintype "passive"))
    )
    (net (code "162") (name "VCC-3V0") (class "Default")
      (node (ref "R50") (pin "1") (pinfunction "1_1") (pintype "passive"))
      (node (ref "R51") (pin "1") (pinfunction "1_1") (pintype "passive"))
      (node (ref "R52") (pin "1") (pinfunction "1_1") (pintype "passive"))
      (node (ref "U4") (pin "43") (pinfunction "VCC-3V0_43") (pintype "passive"))
      (node (ref "U4") (pin "44") (pinfunction "VCC-3V0_44") (pintype "passive"))
    )
    (net (code "163") (name "VCC_3V3") (class "Default")
      (node (ref "C3") (pin "2") (pinfunction "2_2") (pintype "passive"))
      (node (ref "C4") (pin "2") (pinfunction "2_2") (pintype "passive"))
      (node (ref "C40") (pin "1") (pinfunction "1_1") (pintype "passive"))
      (node (ref "C41") (pin "2") (pinfunction "2_2") (pintype "passive"))
      (node (ref "C45") (pin "2") (pinfunction "2_2") (pintype "passive"))
      (node (ref "C46") (pin "2") (pinfunction "2_2") (pintype "passive"))
      (node (ref "C5") (pin "2") (pinfunction "2_2") (pintype "passive"))
      (node (ref "J1") (pin "6") (pinfunction "VCC3.3_6") (pintype "passive"))
      (node (ref "J1") (pin "9") (pinfunction "VCC3.3_9") (pintype "passive"))
      (node (ref "J2") (pin "6") (pinfunction "VCC3.3_6") (pintype "passive"))
      (node (ref "J2") (pin "9") (pinfunction "VCC3.3_9") (pintype "passive"))
      (node (ref "LD1117AG-33-AA3-A-R") (pin "2") (pinfunction "VOUT_2") (pintype "passive"))
    )
    (net (code "164") (name "VCC_3V3A") (class "Default")
      (node (ref "L1") (pin "1") (pinfunction "1_1") (pintype "passive"))
      (node (ref "L2") (pin "1") (pinfunction "1_1") (pintype "passive"))
      (node (ref "L3") (pin "1") (pinfunction "1_1") (pintype "passive"))
    )
    (net (code "165") (name "VCC_3V3_AVDD") (class "Default")
      (node (ref "C43") (pin "1") (pinfunction "1_1") (pintype "passive"))
      (node (ref "C44") (pin "2") (pinfunction "2_2") (pintype "passive"))
      (node (ref "C47") (pin "2") (pinfunction "2_2") (pintype "passive"))
      (node (ref "C48") (pin "2") (pinfunction "2_2") (pintype "passive"))
      (node (ref "L1") (pin "2") (pinfunction "2_2") (pintype "passive"))
      (node (ref "LD1117AG-33") (pin "2") (pinfunction "VOUT_2") (pintype "passive"))
    )
    (net (code "166") (name "unconnected-(*-Pad3)") (class "Default")
      (node (ref "*") (pin "3") (pinfunction "3_3") (pintype "passive"))
    )
    (net (code "167") (name "unconnected-(*-Pad4)") (class "Default")
      (node (ref "*") (pin "4") (pinfunction "4_4") (pintype "passive"))
    )
    (net (code "168") (name "unconnected-(*-Pad12)") (class "Default")
      (node (ref "*") (pin "12") (pinfunction "12_12") (pintype "passive"))
    )
    (net (code "169") (name "unconnected-(*-Pad13)") (class "Default")
      (node (ref "*") (pin "13") (pinfunction "13_13") (pintype "passive"))
    )
    (net (code "170") (name "unconnected-(*-Pad21)") (class "Default")
      (node (ref "*") (pin "21") (pinfunction "21_21") (pintype "passive"))
    )
    (net (code "171") (name "unconnected-(*-Pad22)") (class "Default")
      (node (ref "*") (pin "22") (pinfunction "22_22") (pintype "passive"))
    )
    (net (code "172") (name "unconnected-(*-Pad40)") (class "Default")
      (node (ref "*") (pin "40") (pinfunction "40_40") (pintype "passive"))
    )
    (net (code "173") (name "unconnected-(J1-NC-Pad18)") (class "Default")
      (node (ref "J1") (pin "18") (pinfunction "NC_18") (pintype "passive"))
    )
    (net (code "174") (name "unconnected-(J2-NC-Pad18)") (class "Default")
      (node (ref "J2") (pin "18") (pinfunction "NC_18") (pintype "passive"))
    )
    (net (code "175") (name "unconnected-(J8-N{slash}C-Pad4)") (class "Default")
      (node (ref "J8") (pin "4") (pinfunction "N/C_4") (pintype "passive"))
    )
    (net (code "176") (name "unconnected-(J8-N{slash}C-Pad5)") (class "Default")
      (node (ref "J8") (pin "5") (pinfunction "N/C_5") (pintype "passive"))
    )
    (net (code "177") (name "unconnected-(J8-N{slash}C-Pad7)") (class "Default")
      (node (ref "J8") (pin "7") (pinfunction "N/C_7") (pintype "passive"))
    )
    (net (code "178") (name "unconnected-(U2-D0-Pad32)") (class "Default")
      (node (ref "U2") (pin "32") (pinfunction "D0_32") (pintype "passive"))
    )
    (net (code "179") (name "unconnected-(U2-D1-Pad31)") (class "Default")
      (node (ref "U2") (pin "31") (pinfunction "D1_31") (pintype "passive"))
    )
    (net (code "180") (name "unconnected-(U2-D2-Pad30)") (class "Default")
      (node (ref "U2") (pin "30") (pinfunction "D2_30") (pintype "passive"))
    )
    (net (code "181") (name "unconnected-(U2-D3-Pad29)") (class "Default")
      (node (ref "U2") (pin "29") (pinfunction "D3_29") (pintype "passive"))
    )
    (net (code "182") (name "unconnected-(U2-D4-Pad28)") (class "Default")
      (node (ref "U2") (pin "28") (pinfunction "D4_28") (pintype "passive"))
    )
    (net (code "183") (name "unconnected-(U2-D5-Pad27)") (class "Default")
      (node (ref "U2") (pin "27") (pinfunction "D5_27") (pintype "passive"))
    )
    (net (code "184") (name "unconnected-(U2-D6-Pad25)") (class "Default")
      (node (ref "U2") (pin "25") (pinfunction "D6_25") (pintype "passive"))
    )
    (net (code "185") (name "unconnected-(U2-D7-Pad24)") (class "Default")
      (node (ref "U2") (pin "24") (pinfunction "D7_24") (pintype "passive"))
    )
    (net (code "186") (name "unconnected-(U4-AGND-Pad118)") (class "Default")
      (node (ref "U4") (pin "118") (pinfunction "AGND_118") (pintype "passive"))
    )
    (net (code "187") (name "unconnected-(U4-AP-UART1-CTS-Pad139)") (class "Default")
      (node (ref "U4") (pin "139") (pinfunction "AP-UART1-CTS_139") (pintype "passive"))
    )
    (net (code "188") (name "unconnected-(U4-AP-UART1-RTS-Pad137)") (class "Default")
      (node (ref "U4") (pin "137") (pinfunction "AP-UART1-RTS_137") (pintype "passive"))
    )
    (net (code "189") (name "unconnected-(U4-AP-UART1-RX-Pad138)") (class "Default")
      (node (ref "U4") (pin "138") (pinfunction "AP-UART1-RX_138") (pintype "passive"))
    )
    (net (code "190") (name "unconnected-(U4-AP-UART1-TX-Pad140)") (class "Default")
      (node (ref "U4") (pin "140") (pinfunction "AP-UART1-TX_140") (pintype "passive"))
    )
    (net (code "191") (name "unconnected-(U4-AP-UART2-CTS-Pad129)") (class "Default")
      (node (ref "U4") (pin "129") (pinfunction "AP-UART2-CTS_129") (pintype "passive"))
    )
    (net (code "192") (name "unconnected-(U4-AP-UART2-RTS-Pad130)") (class "Default")
      (node (ref "U4") (pin "130") (pinfunction "AP-UART2-RTS_130") (pintype "passive"))
    )
    (net (code "193") (name "unconnected-(U4-AP-WAKE-BB-Pad136)") (class "Default")
      (node (ref "U4") (pin "136") (pinfunction "AP-WAKE-BB_136") (pintype "passive"))
    )
    (net (code "194") (name "unconnected-(U4-AVDD-CSI-Pad45)") (class "Default")
      (node (ref "U4") (pin "45") (pinfunction "AVDD-CSI_45") (pintype "passive"))
    )
    (net (code "195") (name "unconnected-(U4-BB-PWR-BAT-Pad103)") (class "Default")
      (node (ref "U4") (pin "103") (pinfunction "BB-PWR-BAT_103") (pintype "passive"))
    )
    (net (code "196") (name "unconnected-(U4-BB-PWREN-Pad109)") (class "Default")
      (node (ref "U4") (pin "109") (pinfunction "BB-PWREN_109") (pintype "passive"))
    )
    (net (code "197") (name "unconnected-(U4-BB-RST-Pad102)") (class "Default")
      (node (ref "U4") (pin "102") (pinfunction "BB-RST_102") (pintype "passive"))
    )
    (net (code "198") (name "unconnected-(U4-BB-WAKE-AP-Pad110)") (class "Default")
      (node (ref "U4") (pin "110") (pinfunction "BB-WAKE-AP_110") (pintype "passive"))
    )
    (net (code "199") (name "unconnected-(U4-BT-RST-N-Pad101)") (class "Default")
      (node (ref "U4") (pin "101") (pinfunction "BT-RST-N_101") (pintype "passive"))
    )
    (net (code "200") (name "unconnected-(U4-BT-WAKE-AP-Pad100)") (class "Default")
      (node (ref "U4") (pin "100") (pinfunction "BT-WAKE-AP_100") (pintype "passive"))
    )
    (net (code "201") (name "unconnected-(U4-BT-WAKE-AP-Pad106)") (class "Default")
      (node (ref "U4") (pin "106") (pinfunction "BT-WAKE-AP_106") (pintype "passive"))
    )
    (net (code "202") (name "unconnected-(U4-CSI-MCLK-Pad48)") (class "Default")
      (node (ref "U4") (pin "48") (pinfunction "CSI-MCLK_48") (pintype "passive"))
    )
    (net (code "203") (name "unconnected-(U4-CSI-RST-F-Pad52)") (class "Default")
      (node (ref "U4") (pin "52") (pinfunction "CSI-RST-F_52") (pintype "passive"))
    )
    (net (code "204") (name "unconnected-(U4-CSI-RST-R-Pad54)") (class "Default")
      (node (ref "U4") (pin "54") (pinfunction "CSI-RST-R_54") (pintype "passive"))
    )
    (net (code "205") (name "unconnected-(U4-CSI-SCK-Pad64)") (class "Default")
      (node (ref "U4") (pin "64") (pinfunction "CSI-SCK_64") (pintype "passive"))
    )
    (net (code "206") (name "unconnected-(U4-CSI-SDA-Pad63)") (class "Default")
      (node (ref "U4") (pin "63") (pinfunction "CSI-SDA_63") (pintype "passive"))
    )
    (net (code "207") (name "unconnected-(U4-CSI-STBY-F-Pad51)") (class "Default")
      (node (ref "U4") (pin "51") (pinfunction "CSI-STBY-F_51") (pintype "passive"))
    )
    (net (code "208") (name "unconnected-(U4-CSI-STBY-R-Pad53)") (class "Default")
      (node (ref "U4") (pin "53") (pinfunction "CSI-STBY-R_53") (pintype "passive"))
    )
    (net (code "209") (name "unconnected-(U4-DOVDD-CSI-Pad38)") (class "Default")
      (node (ref "U4") (pin "38") (pinfunction "DOVDD-CSI_38") (pintype "passive"))
    )
    (net (code "210") (name "unconnected-(U4-DSI-CKN-Pad69)") (class "Default")
      (node (ref "U4") (pin "69") (pinfunction "DSI-CKN_69") (pintype "passive"))
    )
    (net (code "211") (name "unconnected-(U4-DSI-CKP-Pad68)") (class "Default")
      (node (ref "U4") (pin "68") (pinfunction "DSI-CKP_68") (pintype "passive"))
    )
    (net (code "212") (name "unconnected-(U4-DSI-D0N-Pad67)") (class "Default")
      (node (ref "U4") (pin "67") (pinfunction "DSI-D0N_67") (pintype "passive"))
    )
    (net (code "213") (name "unconnected-(U4-DSI-D0P-Pad66)") (class "Default")
      (node (ref "U4") (pin "66") (pinfunction "DSI-D0P_66") (pintype "passive"))
    )
    (net (code "214") (name "unconnected-(U4-DSI-D1N-Pad71)") (class "Default")
      (node (ref "U4") (pin "71") (pinfunction "DSI-D1N_71") (pintype "passive"))
    )
    (net (code "215") (name "unconnected-(U4-DSI-D1P-Pad70)") (class "Default")
      (node (ref "U4") (pin "70") (pinfunction "DSI-D1P_70") (pintype "passive"))
    )
    (net (code "216") (name "unconnected-(U4-DSI-D2N-Pad73)") (class "Default")
      (node (ref "U4") (pin "73") (pinfunction "DSI-D2N_73") (pintype "passive"))
    )
    (net (code "217") (name "unconnected-(U4-DSI-D2P-Pad72)") (class "Default")
      (node (ref "U4") (pin "72") (pinfunction "DSI-D2P_72") (pintype "passive"))
    )
    (net (code "218") (name "unconnected-(U4-DSI-D3N-Pad75)") (class "Default")
      (node (ref "U4") (pin "75") (pinfunction "DSI-D3N_75") (pintype "passive"))
    )
    (net (code "219") (name "unconnected-(U4-DSI-D3P-Pad74)") (class "Default")
      (node (ref "U4") (pin "74") (pinfunction "DSI-D3P_74") (pintype "passive"))
    )
    (net (code "220") (name "unconnected-(U4-DVDD1V8-CSI-Pad37)") (class "Default")
      (node (ref "U4") (pin "37") (pinfunction "DVDD1V8-CSI_37") (pintype "passive"))
    )
    (net (code "221") (name "unconnected-(U4-GND-Pad15)") (class "Default")
      (node (ref "U4") (pin "15") (pinfunction "GND_15") (pintype "passive"))
    )
    (net (code "222") (name "unconnected-(U4-GS-INT-Pad156)") (class "Default")
      (node (ref "U4") (pin "156") (pinfunction "GS-INT_156") (pintype "passive"))
    )
    (net (code "223") (name "unconnected-(U4-HPCOM-Pad152)") (class "Default")
      (node (ref "U4") (pin "152") (pinfunction "HPCOM_152") (pintype "passive"))
    )
    (net (code "224") (name "unconnected-(U4-HPCOMFB-Pad151)") (class "Default")
      (node (ref "U4") (pin "151") (pinfunction "HPCOMFB_151") (pintype "passive"))
    )
    (net (code "225") (name "unconnected-(U4-HPL-Pad126)") (class "Default")
      (node (ref "U4") (pin "126") (pinfunction "HPL_126") (pintype "passive"))
    )
    (net (code "226") (name "unconnected-(U4-HPR-Pad125)") (class "Default")
      (node (ref "U4") (pin "125") (pinfunction "HPR_125") (pintype "passive"))
    )
    (net (code "227") (name "unconnected-(U4-LCD-PWM-Pad134)") (class "Default")
      (node (ref "U4") (pin "134") (pinfunction "LCD-PWM_134") (pintype "passive"))
    )
    (net (code "228") (name "unconnected-(U4-LRADC0-Pad104)") (class "Default")
      (node (ref "U4") (pin "104") (pinfunction "LRADC0_104") (pintype "passive"))
    )
    (net (code "229") (name "unconnected-(U4-LS-INT-Pad155)") (class "Default")
      (node (ref "U4") (pin "155") (pinfunction "LS-INT_155") (pintype "passive"))
    )
    (net (code "230") (name "unconnected-(U4-MIC-HBIAS-Pad150)") (class "Default")
      (node (ref "U4") (pin "150") (pinfunction "MIC-HBIAS_150") (pintype "passive"))
    )
    (net (code "231") (name "unconnected-(U4-MIC-MBIAS-Pad149)") (class "Default")
      (node (ref "U4") (pin "149") (pinfunction "MIC-MBIAS_149") (pintype "passive"))
    )
    (net (code "232") (name "unconnected-(U4-MIC1N-Pad123)") (class "Default")
      (node (ref "U4") (pin "123") (pinfunction "MIC1N_123") (pintype "passive"))
    )
    (net (code "233") (name "unconnected-(U4-MIC1P-Pad124)") (class "Default")
      (node (ref "U4") (pin "124") (pinfunction "MIC1P_124") (pintype "passive"))
    )
    (net (code "234") (name "unconnected-(U4-MIC2N-Pad121)") (class "Default")
      (node (ref "U4") (pin "121") (pinfunction "MIC2N_121") (pintype "passive"))
    )
    (net (code "235") (name "unconnected-(U4-MIC2P-Pad122)") (class "Default")
      (node (ref "U4") (pin "122") (pinfunction "MIC2P_122") (pintype "passive"))
    )
    (net (code "236") (name "unconnected-(U4-MT-DRV-N-Pad29)") (class "Default")
      (node (ref "U4") (pin "29") (pinfunction "MT-DRV-N_29") (pintype "passive"))
    )
    (net (code "237") (name "unconnected-(U4-PA-SHDN-Pad158)") (class "Default")
      (node (ref "U4") (pin "158") (pinfunction "PA-SHDN_158") (pintype "passive"))
    )
    (net (code "238") (name "unconnected-(U4-PG11-Pad135)") (class "Default")
      (node (ref "U4") (pin "135") (pinfunction "PG11_135") (pintype "passive"))
    )
    (net (code "239") (name "unconnected-(U4-PG12-Pad3)") (class "Default")
      (node (ref "U4") (pin "3") (pinfunction "PG12_3") (pintype "passive"))
    )
    (net (code "240") (name "unconnected-(U4-PG13-Pad5)") (class "Default")
      (node (ref "U4") (pin "5") (pinfunction "PG13_5") (pintype "passive"))
    )
    (net (code "241") (name "unconnected-(U4-PHINN-Pad148)") (class "Default")
      (node (ref "U4") (pin "148") (pinfunction "PHINN_148") (pintype "passive"))
    )
    (net (code "242") (name "unconnected-(U4-PHINP-Pad147)") (class "Default")
      (node (ref "U4") (pin "147") (pinfunction "PHINP_147") (pintype "passive"))
    )
    (net (code "243") (name "unconnected-(U4-PHOUTN-Pad119)") (class "Default")
      (node (ref "U4") (pin "119") (pinfunction "PHOUTN_119") (pintype "passive"))
    )
    (net (code "244") (name "unconnected-(U4-PHOUTP-Pad120)") (class "Default")
      (node (ref "U4") (pin "120") (pinfunction "PHOUTP_120") (pintype "passive"))
    )
    (net (code "245") (name "unconnected-(U4-POWER_ON_OFF-Pad30)") (class "Default")
      (node (ref "U4") (pin "30") (pinfunction "POWER_ON_OFF_30") (pintype "passive"))
    )
    (net (code "246") (name "unconnected-(U4-PS-Pad27)") (class "Default")
      (node (ref "U4") (pin "27") (pinfunction "PS_27") (pintype "passive"))
    )
    (net (code "247") (name "unconnected-(U4-PS-Pad28)") (class "Default")
      (node (ref "U4") (pin "28") (pinfunction "PS_28") (pintype "passive"))
    )
    (net (code "248") (name "unconnected-(U4-SDC0-CLK-Pad14)") (class "Default")
      (node (ref "U4") (pin "14") (pinfunction "SDC0-CLK_14") (pintype "passive"))
    )
    (net (code "249") (name "unconnected-(U4-SDC0-CMD-Pad13)") (class "Default")
      (node (ref "U4") (pin "13") (pinfunction "SDC0-CMD_13") (pintype "passive"))
    )
    (net (code "250") (name "unconnected-(U4-SDC0-D0-Pad11)") (class "Default")
      (node (ref "U4") (pin "11") (pinfunction "SDC0-D0_11") (pintype "passive"))
    )
    (net (code "251") (name "unconnected-(U4-SDC0-D1-Pad12)") (class "Default")
      (node (ref "U4") (pin "12") (pinfunction "SDC0-D1_12") (pintype "passive"))
    )
    (net (code "252") (name "unconnected-(U4-SDC0-D2-Pad17)") (class "Default")
      (node (ref "U4") (pin "17") (pinfunction "SDC0-D2_17") (pintype "passive"))
    )
    (net (code "253") (name "unconnected-(U4-SDC0-D3-Pad16)") (class "Default")
      (node (ref "U4") (pin "16") (pinfunction "SDC0-D3_16") (pintype "passive"))
    )
    (net (code "254") (name "unconnected-(U4-SENSOR-SCK-Pad4)") (class "Default")
      (node (ref "U4") (pin "4") (pinfunction "SENSOR-SCK_4") (pintype "passive"))
    )
    (net (code "255") (name "unconnected-(U4-SENSOR-SDA-Pad6)") (class "Default")
      (node (ref "U4") (pin "6") (pinfunction "SENSOR-SDA_6") (pintype "passive"))
    )
    (net (code "256") (name "unconnected-(U4-T-CARD-DET-Pad154)") (class "Default")
      (node (ref "U4") (pin "154") (pinfunction "T-CARD-DET_154") (pintype "passive"))
    )
    (net (code "257") (name "unconnected-(U4-TS-Pad41)") (class "Default")
      (node (ref "U4") (pin "41") (pinfunction "TS_41") (pintype "passive"))
    )
    (net (code "258") (name "unconnected-(U4-USB-DM0-Pad115)") (class "Default")
      (node (ref "U4") (pin "115") (pinfunction "USB-DM0_115") (pintype "passive"))
    )
    (net (code "259") (name "unconnected-(U4-USB-DP0-Pad116)") (class "Default")
      (node (ref "U4") (pin "116") (pinfunction "USB-DP0_116") (pintype "passive"))
    )
    (net (code "260") (name "unconnected-(U4-USB-DRVVBUS-Pad31)") (class "Default")
      (node (ref "U4") (pin "31") (pinfunction "USB-DRVVBUS_31") (pintype "passive"))
    )
    (net (code "261") (name "unconnected-(U4-USB-ID-Pad157)") (class "Default")
      (node (ref "U4") (pin "157") (pinfunction "USB-ID_157") (pintype "passive"))
    )
    (net (code "262") (name "unconnected-(U4-USBVUBS-Pad25)") (class "Default")
      (node (ref "U4") (pin "25") (pinfunction "USBVUBS_25") (pintype "passive"))
    )
    (net (code "263") (name "unconnected-(U4-VBAT-EXT-Pad23)") (class "Default")
      (node (ref "U4") (pin "23") (pinfunction "VBAT-EXT_23") (pintype "passive"))
    )
    (net (code "264") (name "unconnected-(U4-VBAT-EXT-Pad24)") (class "Default")
      (node (ref "U4") (pin "24") (pinfunction "VBAT-EXT_24") (pintype "passive"))
    )
    (net (code "265") (name "unconnected-(U4-VBAT-Pad21)") (class "Default")
      (node (ref "U4") (pin "21") (pinfunction "VBAT_21") (pintype "passive"))
    )
    (net (code "266") (name "unconnected-(U4-VBAT-Pad22)") (class "Default")
      (node (ref "U4") (pin "22") (pinfunction "VBAT_22") (pintype "passive"))
    )
    (net (code "267") (name "unconnected-(U4-VCC-CTP-Pad42)") (class "Default")
      (node (ref "U4") (pin "42") (pinfunction "VCC-CTP_42") (pintype "passive"))
    )
    (net (code "268") (name "unconnected-(U4-VCC-MOTOR-Pad40)") (class "Default")
      (node (ref "U4") (pin "40") (pinfunction "VCC-MOTOR_40") (pintype "passive"))
    )
    (net (code "269") (name "unconnected-(U4-VCC-RTC-Pad18)") (class "Default")
      (node (ref "U4") (pin "18") (pinfunction "VCC-RTC_18") (pintype "passive"))
    )
    (net (code "270") (name "unconnected-(U4-VCC-WIFI-Pad39)") (class "Default")
      (node (ref "U4") (pin "39") (pinfunction "VCC-WIFI_39") (pintype "passive"))
    )
    (net (code "271") (name "unconnected-(U4-WL-PMU-EN-Pad108)") (class "Default")
      (node (ref "U4") (pin "108") (pinfunction "WL-PMU-EN_108") (pintype "passive"))
    )
    (net (code "272") (name "unconnected-(U4-WL-RST-N-Pad105)") (class "Default")
      (node (ref "U4") (pin "105") (pinfunction "WL-RST-N_105") (pintype "passive"))
    )
    (net (code "273") (name "unconnected-(U4-WL-SDIO-CLK-Pad142)") (class "Default")
      (node (ref "U4") (pin "142") (pinfunction "WL-SDIO-CLK_142") (pintype "passive"))
    )
    (net (code "274") (name "unconnected-(U4-WL-SDIO-CMD-Pad141)") (class "Default")
      (node (ref "U4") (pin "141") (pinfunction "WL-SDIO-CMD_141") (pintype "passive"))
    )
    (net (code "275") (name "unconnected-(U4-WL-SDIO-D0-Pad143)") (class "Default")
      (node (ref "U4") (pin "143") (pinfunction "WL-SDIO-D0_143") (pintype "passive"))
    )
    (net (code "276") (name "unconnected-(U4-WL-SDIO-D1-Pad144)") (class "Default")
      (node (ref "U4") (pin "144") (pinfunction "WL-SDIO-D1_144") (pintype "passive"))
    )
    (net (code "277") (name "unconnected-(U4-WL-SDIO-D2-Pad145)") (class "Default")
      (node (ref "U4") (pin "145") (pinfunction "WL-SDIO-D2_145") (pintype "passive"))
    )
    (net (code "278") (name "unconnected-(U4-WL-SDIO-D3-Pad146)") (class "Default")
      (node (ref "U4") (pin "146") (pinfunction "WL-SDIO-D3_146") (pintype "passive"))
    )
    (net (code "279") (name "unconnected-(U4-WL-WAKE-AP-Pad107)") (class "Default")
      (node (ref "U4") (pin "107") (pinfunction "WL-WAKE-AP_107") (pintype "passive"))
    )
    (net (code "280") (name "unconnected-(U5-NC-Pad4)") (class "Default")
      (node (ref "U5") (pin "4") (pinfunction "NC_4") (pintype "passive"))
    )
    (net (code "281") (name "unconnected-(U8-OVCUR2-Pad19)") (class "Default")
      (node (ref "U8") (pin "19") (pinfunction "OVCUR2_19") (pintype "passive"))
    )
    (net (code "282") (name "unconnected-(U8-PWREN2-Pad20)") (class "Default")
      (node (ref "U8") (pin "20") (pinfunction "PWREN2_20") (pintype "passive"))
    )
    (net (code "283") (name "unconnected-(U9-CKXTAL1-Pad21)") (class "Default")
      (node (ref "U9") (pin "21") (pinfunction "CKXTAL1_21") (pintype "passive"))
    )
  )
)
